# ProPrj_100MHz__2024-06-24.net
KiCad netlist of a schematic drawn in EasyEDA Pro
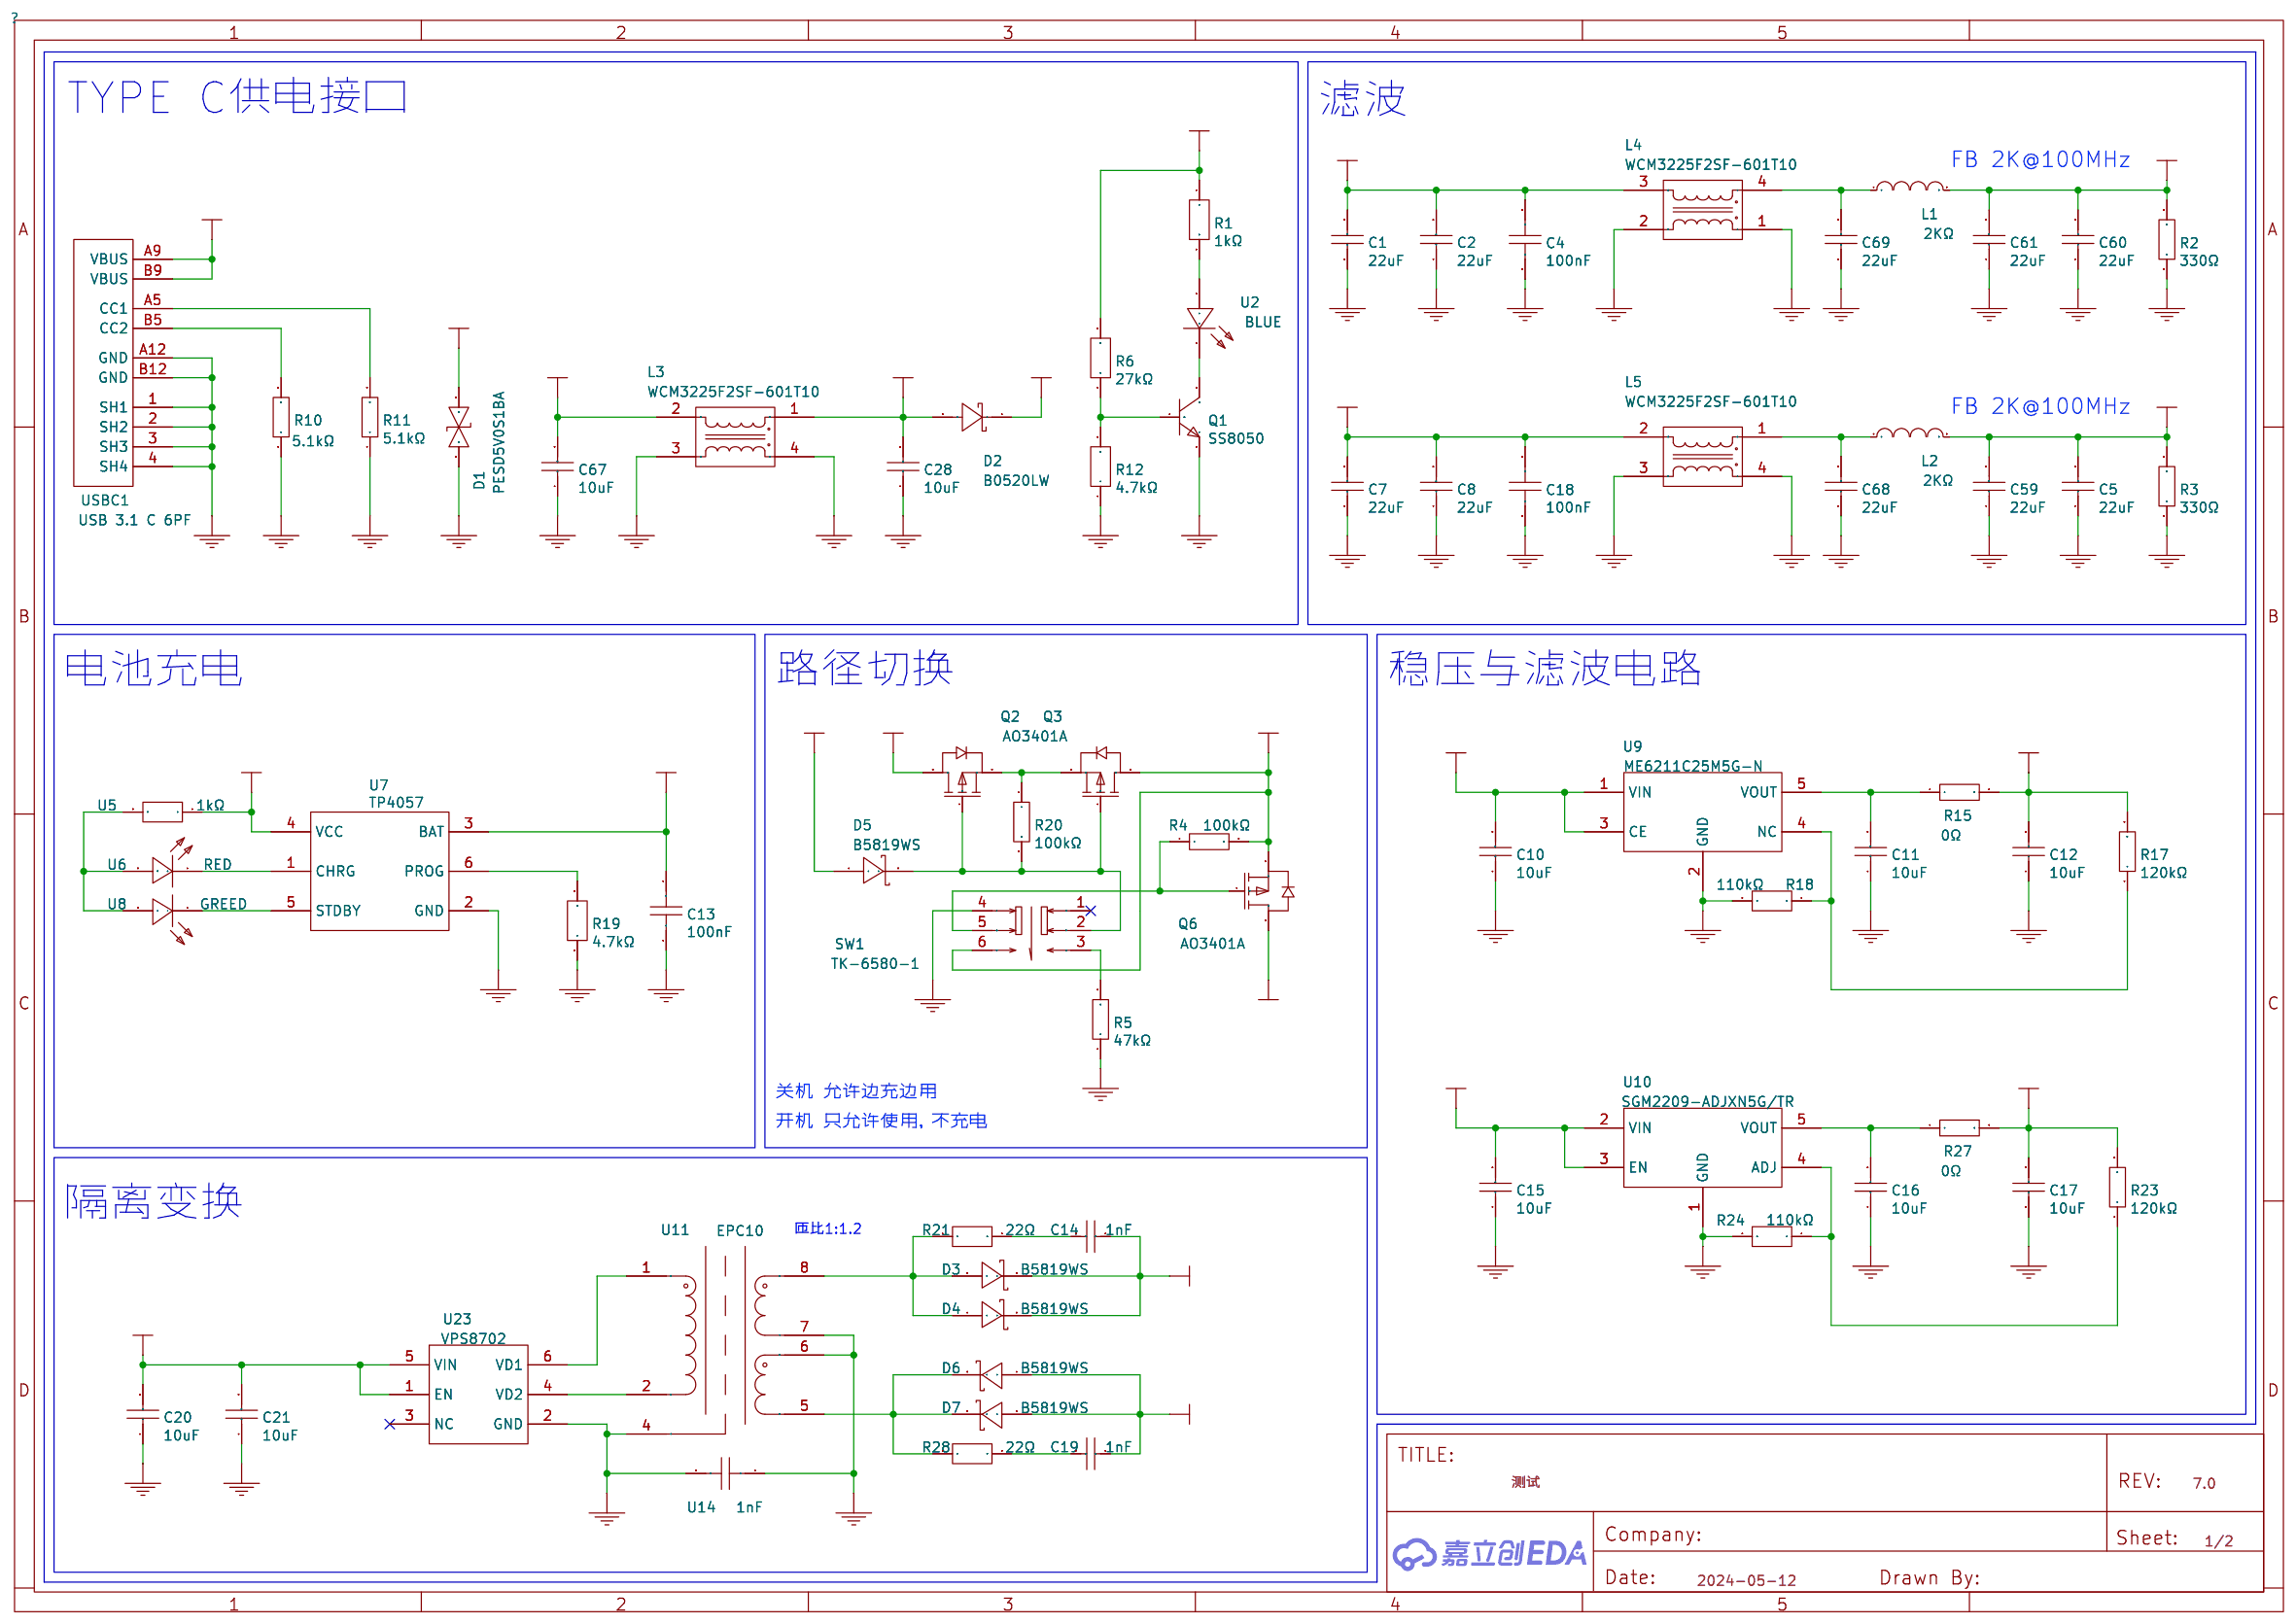
[diagram p0: 充电管理与隔离变换]
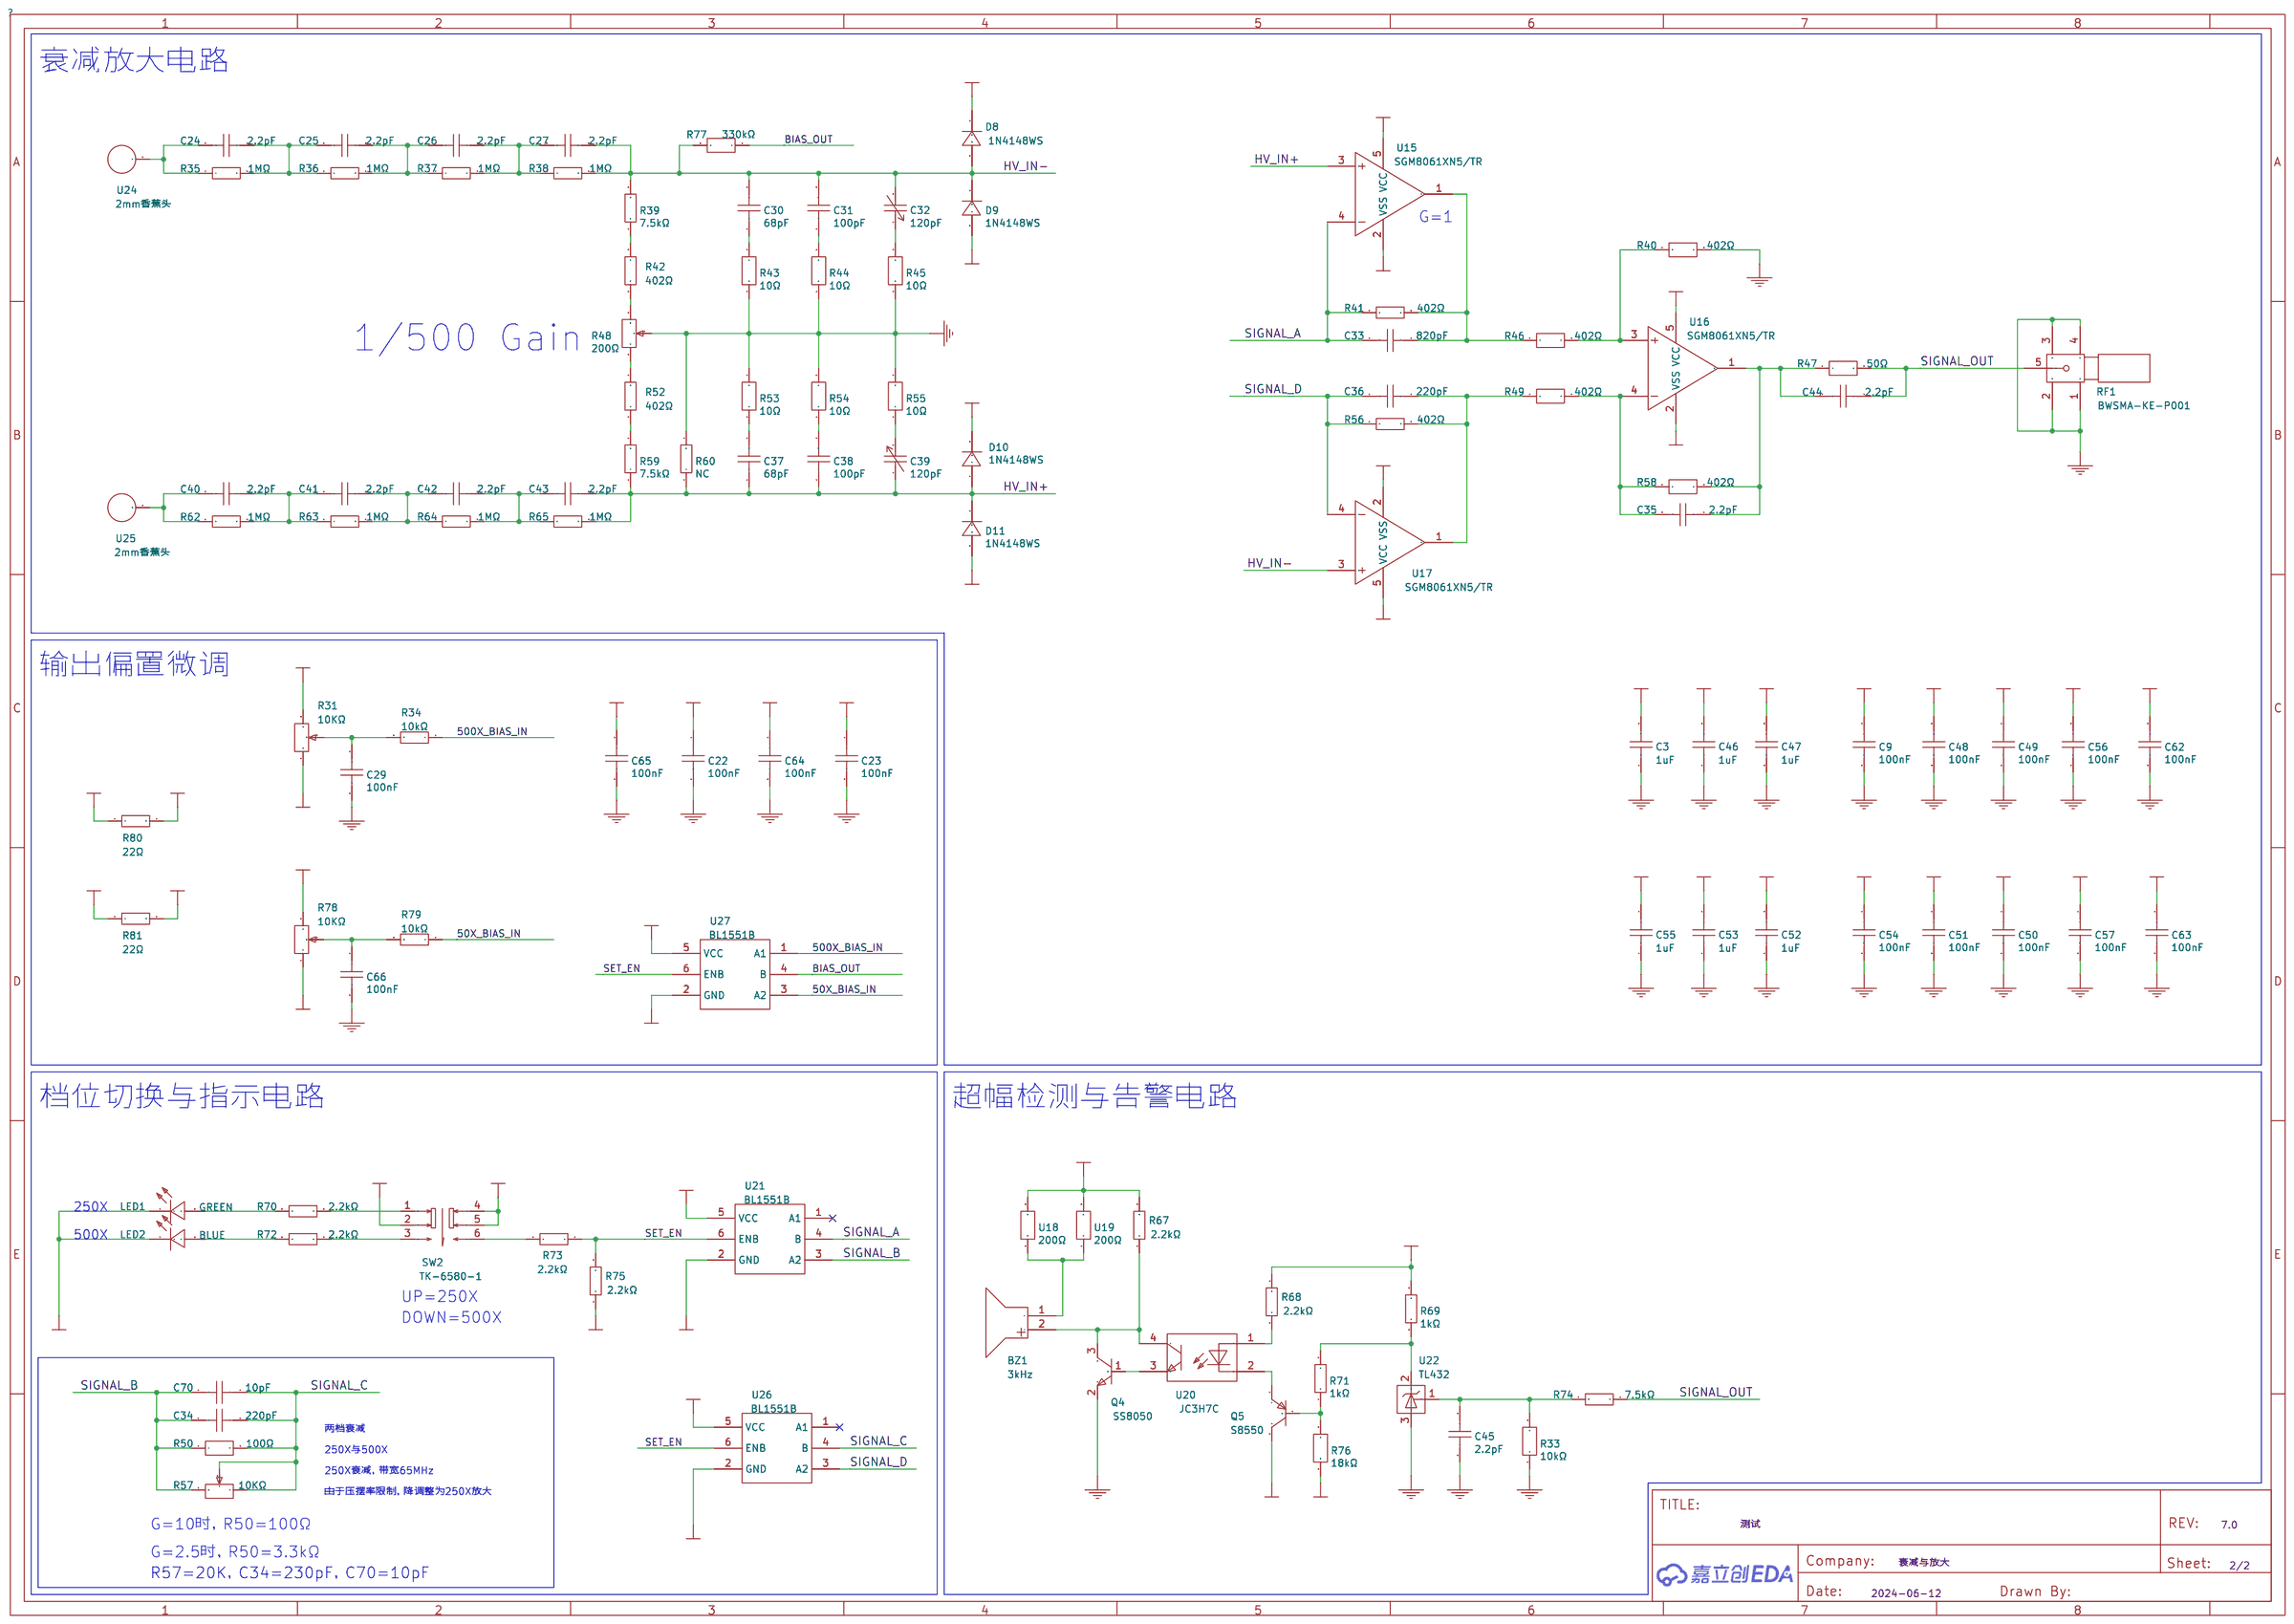
[diagram p1: 衰减与放大]

(export (version "E")
  (design (tool "Eeschema 10.0.6"))
  (components
    (comp (ref "C1")
      (value "22uF")
      (fields
        (field (name "Manufacturer Part") "CC0603MRX5R5BB226")
        (field (name "Manufacturer") "YAGEO(国巨)")
      )
      (libsource (lib "easyedapro") (part "22uF"))
    )
    (comp (ref "C2")
      (value "22uF")
      (fields
        (field (name "Manufacturer Part") "CC0603MRX5R5BB226")
        (field (name "Manufacturer") "YAGEO(国巨)")
      )
      (libsource (lib "easyedapro") (part "22uF"))
    )
    (comp (ref "C4")
      (value "100nF")
      (fields (field (name "Manufacturer Part") "0603B104K160NT") (field (name "Manufacturer") "FH(风华)"))
      (libsource (lib "easyedapro") (part "100nF"))
    )
    (comp (ref "C5")
      (value "22uF")
      (fields
        (field (name "Manufacturer Part") "CC0603MRX5R5BB226")
        (field (name "Manufacturer") "YAGEO(国巨)")
      )
      (libsource (lib "easyedapro") (part "22uF"))
    )
    (comp (ref "C7")
      (value "22uF")
      (fields
        (field (name "Manufacturer Part") "CC0603MRX5R5BB226")
        (field (name "Manufacturer") "YAGEO(国巨)")
      )
      (libsource (lib "easyedapro") (part "22uF"))
    )
    (comp (ref "C8")
      (value "22uF")
      (fields
        (field (name "Manufacturer Part") "CC0603MRX5R5BB226")
        (field (name "Manufacturer") "YAGEO(国巨)")
      )
      (libsource (lib "easyedapro") (part "22uF"))
    )
    (comp (ref "C10")
      (value "10uF")
      (fields
        (field (name "Manufacturer Part") "CC0603MRX5R5BB106")
        (field (name "Manufacturer") "YAGEO(国巨)")
      )
      (libsource (lib "easyedapro") (part "10uF"))
    )
    (comp (ref "C11")
      (value "10uF")
      (fields
        (field (name "Manufacturer Part") "CC0603MRX5R5BB106")
        (field (name "Manufacturer") "YAGEO(国巨)")
      )
      (libsource (lib "easyedapro") (part "10uF"))
    )
    (comp (ref "C12")
      (value "10uF")
      (fields
        (field (name "Manufacturer Part") "CC0603MRX5R5BB106")
        (field (name "Manufacturer") "YAGEO(国巨)")
      )
      (libsource (lib "easyedapro") (part "10uF"))
    )
    (comp (ref "C13")
      (value "100nF")
      (fields (field (name "Manufacturer Part") "0603B104K160NT") (field (name "Manufacturer") "FH(风华)"))
      (libsource (lib "easyedapro") (part "100nF"))
    )
    (comp (ref "C14")
      (value "1nF")
      (fields (field (name "Manufacturer Part") "0603CG102F500NT") (field (name "Manufacturer") "FH(风华)"))
      (libsource (lib "easyedapro") (part "1nF"))
    )
    (comp (ref "C15")
      (value "10uF")
      (fields
        (field (name "Manufacturer Part") "CC0603MRX5R5BB106")
        (field (name "Manufacturer") "YAGEO(国巨)")
      )
      (libsource (lib "easyedapro") (part "10uF"))
    )
    (comp (ref "C16")
      (value "10uF")
      (fields
        (field (name "Manufacturer Part") "CC0603MRX5R5BB106")
        (field (name "Manufacturer") "YAGEO(国巨)")
      )
      (libsource (lib "easyedapro") (part "10uF"))
    )
    (comp (ref "C17")
      (value "10uF")
      (fields
        (field (name "Manufacturer Part") "CC0603MRX5R5BB106")
        (field (name "Manufacturer") "YAGEO(国巨)")
      )
      (libsource (lib "easyedapro") (part "10uF"))
    )
    (comp (ref "C18")
      (value "100nF")
      (fields (field (name "Manufacturer Part") "0603B104K160NT") (field (name "Manufacturer") "FH(风华)"))
      (libsource (lib "easyedapro") (part "100nF"))
    )
    (comp (ref "C19")
      (value "1nF")
      (fields (field (name "Manufacturer Part") "0603CG102F500NT") (field (name "Manufacturer") "FH(风华)"))
      (libsource (lib "easyedapro") (part "1nF"))
    )
    (comp (ref "C20")
      (value "10uF")
      (fields
        (field (name "Manufacturer Part") "CC0603MRX5R5BB106")
        (field (name "Manufacturer") "YAGEO(国巨)")
      )
      (libsource (lib "easyedapro") (part "10uF"))
    )
    (comp (ref "C21")
      (value "10uF")
      (fields
        (field (name "Manufacturer Part") "CC0603MRX5R5BB106")
        (field (name "Manufacturer") "YAGEO(国巨)")
      )
      (libsource (lib "easyedapro") (part "10uF"))
    )
    (comp (ref "C28")
      (value "10uF")
      (fields
        (field (name "Manufacturer Part") "CC0603MRX5R5BB106")
        (field (name "Manufacturer") "YAGEO(国巨)")
      )
      (libsource (lib "easyedapro") (part "10uF"))
    )
    (comp (ref "C59")
      (value "22uF")
      (fields
        (field (name "Manufacturer Part") "CC0603MRX5R5BB226")
        (field (name "Manufacturer") "YAGEO(国巨)")
      )
      (libsource (lib "easyedapro") (part "22uF"))
    )
    (comp (ref "C60")
      (value "22uF")
      (fields
        (field (name "Manufacturer Part") "CC0603MRX5R5BB226")
        (field (name "Manufacturer") "YAGEO(国巨)")
      )
      (libsource (lib "easyedapro") (part "22uF"))
    )
    (comp (ref "C61")
      (value "22uF")
      (fields
        (field (name "Manufacturer Part") "CC0603MRX5R5BB226")
        (field (name "Manufacturer") "YAGEO(国巨)")
      )
      (libsource (lib "easyedapro") (part "22uF"))
    )
    (comp (ref "C67")
      (value "10uF")
      (fields
        (field (name "Manufacturer Part") "CC0603MRX5R5BB106")
        (field (name "Manufacturer") "YAGEO(国巨)")
      )
      (libsource (lib "easyedapro") (part "10uF"))
    )
    (comp (ref "C68")
      (value "22uF")
      (fields
        (field (name "Manufacturer Part") "CC0603MRX5R5BB226")
        (field (name "Manufacturer") "YAGEO(国巨)")
      )
      (libsource (lib "easyedapro") (part "22uF"))
    )
    (comp (ref "C69")
      (value "22uF")
      (fields
        (field (name "Manufacturer Part") "CC0603MRX5R5BB226")
        (field (name "Manufacturer") "YAGEO(国巨)")
      )
      (libsource (lib "easyedapro") (part "22uF"))
    )
    (comp (ref "D1")
      (value "PESD5V0S1BA")
      (fields (field (name "Manufacturer") "TECH PUBLIC(台舟)"))
      (libsource (lib "easyedapro") (part "PESD5V0S1BA"))
    )
    (comp (ref "D2")
      (value "B0520LW")
      (fields (field (name "Manufacturer") "CJ(江苏长电/长晶)"))
      (libsource (lib "easyedapro") (part "B0520LW"))
    )
    (comp (ref "D3")
      (value "B5819WS")
      (fields (field (name "Manufacturer") "CJ(江苏长电/长晶)"))
      (libsource (lib "easyedapro") (part "B5819WS"))
    )
    (comp (ref "D4")
      (value "B5819WS")
      (fields (field (name "Manufacturer") "CJ(江苏长电/长晶)"))
      (libsource (lib "easyedapro") (part "B5819WS"))
    )
    (comp (ref "D5")
      (value "B5819WS")
      (fields (field (name "Manufacturer") "CJ(江苏长电/长晶)"))
      (libsource (lib "easyedapro") (part "B5819WS"))
    )
    (comp (ref "D6")
      (value "B5819WS")
      (fields (field (name "Manufacturer") "CJ(江苏长电/长晶)"))
      (libsource (lib "easyedapro") (part "B5819WS"))
    )
    (comp (ref "D7")
      (value "B5819WS")
      (fields (field (name "Manufacturer") "CJ(江苏长电/长晶)"))
      (libsource (lib "easyedapro") (part "B5819WS"))
    )
    (comp (ref "L1")
      (value "2KΩ")
      (fields (field (name "Manufacturer Part") "GZ1608D202TF") (field (name "Manufacturer") "Sunlord(顺络)"))
      (libsource (lib "easyedapro") (part "2KΩ"))
    )
    (comp (ref "L2")
      (value "2KΩ")
      (fields (field (name "Manufacturer Part") "GZ1608D202TF") (field (name "Manufacturer") "Sunlord(顺络)"))
      (libsource (lib "easyedapro") (part "2KΩ"))
    )
    (comp (ref "L3")
      (value "WCM3225F2SF-601T10")
      (footprint "easyedapro:FILTER-SMD_4P-L3.2-W2.5-TL-1")
      (description "线路数:2;阻抗 @ 频率:600Ω@100MHz;直流电阻(DCR):200mΩ;")
      (fields (field (name "Manufacturer") "TAI-TECH(台庆)"))
      (libsource (lib "easyedapro") (part "WCM3225F2SF-601T10"))
    )
    (comp (ref "L4")
      (value "WCM3225F2SF-601T10")
      (footprint "easyedapro:FILTER-SMD_4P-L3.2-W2.5-TL-1")
      (description "线路数:2;阻抗 @ 频率:600Ω@100MHz;直流电阻(DCR):200mΩ;")
      (fields (field (name "Manufacturer") "TAI-TECH(台庆)"))
      (libsource (lib "easyedapro") (part "WCM3225F2SF-601T10"))
    )
    (comp (ref "L5")
      (value "WCM3225F2SF-601T10")
      (footprint "easyedapro:FILTER-SMD_4P-L3.2-W2.5-TL-1")
      (description "线路数:2;阻抗 @ 频率:600Ω@100MHz;直流电阻(DCR):200mΩ;")
      (fields (field (name "Manufacturer") "TAI-TECH(台庆)"))
      (libsource (lib "easyedapro") (part "WCM3225F2SF-601T10"))
    )
    (comp (ref "Q1")
      (value "SS8050")
      (fields (field (name "Manufacturer Part") "SS8050-G") (field (name "Manufacturer") "CJ(江苏长电/长晶)"))
      (libsource (lib "easyedapro") (part "SS8050"))
    )
    (comp (ref "Q2")
      (value "AO3401A")
      (fields (field (name "Manufacturer") "UMW(友台半导体)"))
      (libsource (lib "") (part "AO3401A_2"))
    )
    (comp (ref "Q3")
      (value "AO3401A")
      (fields (field (name "Manufacturer") "UMW(友台半导体)"))
      (libsource (lib "easyedapro") (part "AO3401A"))
    )
    (comp (ref "Q6")
      (value "AO3401A")
      (fields (field (name "Manufacturer") "UMW(友台半导体)"))
      (libsource (lib "") (part "AO3401A_1"))
    )
    (comp (ref "R1")
      (value "1kΩ")
      (fields (field (name "Manufacturer Part") "RT0603BRB071KL") (field (name "Manufacturer") "YAGEO(国巨)"))
      (libsource (lib "easyedapro") (part "1kΩ"))
    )
    (comp (ref "R2")
      (value "330Ω")
      (fields (field (name "Manufacturer Part") "AF0603FR-07330RL") (field (name "Manufacturer") "YAGEO(国巨)"))
      (libsource (lib "easyedapro") (part "330Ω"))
    )
    (comp (ref "R3")
      (value "330Ω")
      (fields (field (name "Manufacturer Part") "AF0603FR-07330RL") (field (name "Manufacturer") "YAGEO(国巨)"))
      (libsource (lib "easyedapro") (part "330Ω"))
    )
    (comp (ref "R4")
      (value "100kΩ")
      (fields (field (name "Manufacturer Part") "AF0603JR-07100KL") (field (name "Manufacturer") "YAGEO(国巨)"))
      (libsource (lib "easyedapro") (part "100kΩ"))
    )
    (comp (ref "R5")
      (value "47kΩ")
      (fields (field (name "Manufacturer Part") "AF0603JR-07100KL") (field (name "Manufacturer") "YAGEO(国巨)"))
      (libsource (lib "easyedapro") (part "47kΩ"))
    )
    (comp (ref "R6")
      (value "27kΩ")
      (fields (field (name "Manufacturer Part") "AC0603DR-0727KL") (field (name "Manufacturer") "YAGEO(国巨)"))
      (libsource (lib "easyedapro") (part "27kΩ"))
    )
    (comp (ref "R10")
      (value "5.1kΩ")
      (fields
        (field (name "Manufacturer Part") "0603WAF5101T5E")
        (field (name "Manufacturer") "UNI-ROYAL(厚声)")
      )
      (libsource (lib "easyedapro") (part "5.1kΩ"))
    )
    (comp (ref "R11")
      (value "5.1kΩ")
      (fields
        (field (name "Manufacturer Part") "0603WAF5101T5E")
        (field (name "Manufacturer") "UNI-ROYAL(厚声)")
      )
      (libsource (lib "easyedapro") (part "5.1kΩ"))
    )
    (comp (ref "R12")
      (value "4.7kΩ")
      (fields (field (name "Manufacturer Part") "RT0603CRE074K7L") (field (name "Manufacturer") "YAGEO(国巨)"))
      (libsource (lib "easyedapro") (part "4.7kΩ"))
    )
    (comp (ref "R15")
      (value "0Ω")
      (fields (field (name "Manufacturer Part") "RC0603FR-070RL") (field (name "Manufacturer") "YAGEO(国巨)"))
      (libsource (lib "easyedapro") (part "0Ω"))
    )
    (comp (ref "R17")
      (value "120kΩ")
      (fields
        (field (name "Manufacturer Part") "AC0603FR-07120KL")
        (field (name "Manufacturer") "UNI-ROYAL(厚声)")
      )
      (libsource (lib "easyedapro") (part "120kΩ"))
    )
    (comp (ref "R18")
      (value "110kΩ")
      (fields
        (field (name "Manufacturer Part") "0603WAD1103T5E")
        (field (name "Manufacturer") "UNI-ROYAL(厚声)")
      )
      (libsource (lib "easyedapro") (part "110kΩ"))
    )
    (comp (ref "R19")
      (value "4.7kΩ")
      (fields (field (name "Manufacturer Part") "RT0603CRE074K7L") (field (name "Manufacturer") "YAGEO(国巨)"))
      (libsource (lib "easyedapro") (part "4.7kΩ"))
    )
    (comp (ref "R20")
      (value "100kΩ")
      (fields (field (name "Manufacturer Part") "AF0603JR-07100KL") (field (name "Manufacturer") "YAGEO(国巨)"))
      (libsource (lib "easyedapro") (part "100kΩ"))
    )
    (comp (ref "R21")
      (value "22Ω")
      (fields (field (name "Manufacturer Part") "AC0603DR-0722RL") (field (name "Manufacturer") "YAGEO(国巨)"))
      (libsource (lib "easyedapro") (part "22Ω"))
    )
    (comp (ref "R23")
      (value "120kΩ")
      (fields
        (field (name "Manufacturer Part") "AC0603FR-07120KL")
        (field (name "Manufacturer") "UNI-ROYAL(厚声)")
      )
      (libsource (lib "easyedapro") (part "120kΩ"))
    )
    (comp (ref "R24")
      (value "110kΩ")
      (fields
        (field (name "Manufacturer Part") "0603WAD1103T5E")
        (field (name "Manufacturer") "UNI-ROYAL(厚声)")
      )
      (libsource (lib "easyedapro") (part "110kΩ"))
    )
    (comp (ref "R27")
      (value "0Ω")
      (fields (field (name "Manufacturer Part") "RC0603FR-070RL") (field (name "Manufacturer") "YAGEO(国巨)"))
      (libsource (lib "easyedapro") (part "0Ω"))
    )
    (comp (ref "R28")
      (value "22Ω")
      (fields (field (name "Manufacturer Part") "AC0603DR-0722RL") (field (name "Manufacturer") "YAGEO(国巨)"))
      (libsource (lib "easyedapro") (part "22Ω"))
    )
    (comp (ref "SW1")
      (value "TK-6580-1")
      (fields (field (name "Manufacturer") "Yuandi(元迪)"))
      (libsource (lib "easyedapro") (part "TK-6580-1"))
    )
    (comp (ref "U2")
      (value "BLUE")
      (fields (field (name "Manufacturer Part") "BLUEled-0603"))
      (libsource (lib "easyedapro") (part "BLUE"))
    )
    (comp (ref "U5")
      (value "1kΩ")
      (fields (field (name "Manufacturer Part") "RT0603BRB071KL") (field (name "Manufacturer") "YAGEO(国巨)"))
      (libsource (lib "easyedapro") (part "1kΩ"))
    )
    (comp (ref "U6")
      (value "RED")
      (fields (field (name "Manufacturer Part") "RED-LED_0603"))
      (libsource (lib "easyedapro") (part "RED"))
    )
    (comp (ref "U7")
      (value "TP4057")
      (fields
        (field (name "Manufacturer Part") "TP4057-42-SOT26-R")
        (field (name "Manufacturer") "TOPPOWER(南京拓微)")
      )
      (libsource (lib "easyedapro") (part "TP4057"))
    )
    (comp (ref "U8")
      (value "GREED")
      (fields (field (name "Manufacturer Part") "NCD0603O3") (field (name "Manufacturer") "国星光电"))
      (libsource (lib "easyedapro") (part "GREED"))
    )
    (comp (ref "U9")
      (value "ME6211C25M5G-N")
      (fields (field (name "Manufacturer") "MICRONE(南京微盟)"))
      (libsource (lib "easyedapro") (part "ME6211C25M5G-N"))
    )
    (comp (ref "U10") (value "SGM2209-ADJXN5G/TR") (libsource (lib "easyedapro") (part "SGM2209-ADJXN5G/TR")))
    (comp (ref "U11") (value "EPC10") (libsource (lib "easyedapro") (part "EPC10")))
    (comp (ref "U14")
      (value "1nF")
      (fields
        (field (name "Manufacturer Part") "SCC1808X102K502T")
        (field (name "Manufacturer") "IHHEC(禾伸堂)")
      )
      (libsource (lib "") (part "1nF_1"))
    )
    (comp (ref "U23")
      (value "VPS8702")
      (fields (field (name "Manufacturer") "VPSC(源特科技)"))
      (libsource (lib "easyedapro") (part "VPS8702"))
    )
    (comp (ref "USBC1")
      (value "USB 3.1 C 6PF")
      (fields (field (name "Manufacturer Part") "918-418K2023S40005") (field (name "Manufacturer") "精拓金"))
      (libsource (lib "easyedapro") (part "USB 3.1 C 6PF"))
    )
    (comp (ref "BZ1")
      (value "3kHz")
      (fields (field (name "Manufacturer Part") "HNB09A03") (field (name "Manufacturer") "华能"))
      (libsource (lib "easyedapro") (part "3kHz"))
    )
    (comp (ref "C3")
      (value "1uF")
      (fields
        (field (name "Manufacturer Part") "AC0603KRX7R6BB105")
        (field (name "Manufacturer") "YAGEO(国巨)")
      )
      (libsource (lib "easyedapro") (part "1uF"))
    )
    (comp (ref "C9")
      (value "100nF")
      (fields (field (name "Manufacturer Part") "0603B104K160NT") (field (name "Manufacturer") "FH(风华)"))
      (libsource (lib "easyedapro") (part "100nF"))
    )
    (comp (ref "C22")
      (value "100nF")
      (fields (field (name "Manufacturer Part") "0603B104K160NT") (field (name "Manufacturer") "FH(风华)"))
      (libsource (lib "easyedapro") (part "100nF"))
    )
    (comp (ref "C23")
      (value "100nF")
      (fields (field (name "Manufacturer Part") "0603B104K160NT") (field (name "Manufacturer") "FH(风华)"))
      (libsource (lib "easyedapro") (part "100nF"))
    )
    (comp (ref "C24")
      (value "2.2pF")
      (fields (field (name "Manufacturer Part") "1206N2R2C102CT") (field (name "Manufacturer") "Walsin(华新科)"))
      (libsource (lib "easyedapro") (part "2.2pF"))
    )
    (comp (ref "C25")
      (value "2.2pF")
      (fields (field (name "Manufacturer Part") "1206N2R2C102CT") (field (name "Manufacturer") "Walsin(华新科)"))
      (libsource (lib "easyedapro") (part "2.2pF"))
    )
    (comp (ref "C26")
      (value "2.2pF")
      (fields (field (name "Manufacturer Part") "1206N2R2C102CT") (field (name "Manufacturer") "Walsin(华新科)"))
      (libsource (lib "easyedapro") (part "2.2pF"))
    )
    (comp (ref "C27")
      (value "2.2pF")
      (fields (field (name "Manufacturer Part") "1206N2R2C102CT") (field (name "Manufacturer") "Walsin(华新科)"))
      (libsource (lib "easyedapro") (part "2.2pF"))
    )
    (comp (ref "C29")
      (value "100nF")
      (fields (field (name "Manufacturer Part") "0603B104K160NT") (field (name "Manufacturer") "FH(风华)"))
      (libsource (lib "easyedapro") (part "100nF"))
    )
    (comp (ref "C30")
      (value "68pF")
      (fields
        (field (name "Manufacturer Part") "CC0603GRNPO9BN680")
        (field (name "Manufacturer") "YAGEO(国巨)")
      )
      (libsource (lib "easyedapro") (part "68pF"))
    )
    (comp (ref "C31")
      (value "100pF")
      (fields
        (field (name "Manufacturer Part") "AC0603JRNPO9BN101")
        (field (name "Manufacturer") "YAGEO(国巨)")
      )
      (libsource (lib "easyedapro") (part "100pF"))
    )
    (comp (ref "C32") (value "120pF") (libsource (lib "easyedapro") (part "120pF")))
    (comp (ref "C33")
      (value "820pF")
      (fields
        (field (name "Manufacturer Part") "CC0603FRNPO0BN220")
        (field (name "Manufacturer") "YAGEO(国巨)")
      )
      (libsource (lib "easyedapro") (part "22pF"))
    )
    (comp (ref "C34")
      (value "220pF")
      (fields
        (field (name "Manufacturer Part") "CC0402JRNPO9BN221")
        (field (name "Manufacturer") "YAGEO(国巨)")
      )
      (libsource (lib "easyedapro") (part "22pF"))
    )
    (comp (ref "C35")
      (value "2.2pF")
      (fields
        (field (name "Manufacturer Part") "CC0603GRNPO0BN100")
        (field (name "Manufacturer") "YAGEO(国巨)")
      )
      (libsource (lib "") (part "10pF_2"))
    )
    (comp (ref "C36")
      (value "220pF")
      (fields
        (field (name "Manufacturer Part") "CC0603FRNPO0BN220")
        (field (name "Manufacturer") "YAGEO(国巨)")
      )
      (libsource (lib "easyedapro") (part "22pF"))
    )
    (comp (ref "C37")
      (value "68pF")
      (fields
        (field (name "Manufacturer Part") "CC0603GRNPO9BN680")
        (field (name "Manufacturer") "YAGEO(国巨)")
      )
      (libsource (lib "easyedapro") (part "68pF"))
    )
    (comp (ref "C38")
      (value "100pF")
      (fields
        (field (name "Manufacturer Part") "AC0603JRNPO9BN101")
        (field (name "Manufacturer") "YAGEO(国巨)")
      )
      (libsource (lib "easyedapro") (part "100pF"))
    )
    (comp (ref "C39") (value "120pF") (libsource (lib "easyedapro") (part "120pF")))
    (comp (ref "C40")
      (value "2.2pF")
      (fields (field (name "Manufacturer Part") "1206N2R2C102CT") (field (name "Manufacturer") "Walsin(华新科)"))
      (libsource (lib "easyedapro") (part "2.2pF"))
    )
    (comp (ref "C41")
      (value "2.2pF")
      (fields (field (name "Manufacturer Part") "1206N2R2C102CT") (field (name "Manufacturer") "Walsin(华新科)"))
      (libsource (lib "easyedapro") (part "2.2pF"))
    )
    (comp (ref "C42")
      (value "2.2pF")
      (fields (field (name "Manufacturer Part") "1206N2R2C102CT") (field (name "Manufacturer") "Walsin(华新科)"))
      (libsource (lib "easyedapro") (part "2.2pF"))
    )
    (comp (ref "C43")
      (value "2.2pF")
      (fields (field (name "Manufacturer Part") "1206N2R2C102CT") (field (name "Manufacturer") "Walsin(华新科)"))
      (libsource (lib "easyedapro") (part "2.2pF"))
    )
    (comp (ref "C44")
      (value "2.2pF")
      (fields
        (field (name "Manufacturer Part") "CC0603GRNPO0BN100")
        (field (name "Manufacturer") "YAGEO(国巨)")
        (field (name "Tolerance") "±2%")
      )
      (libsource (lib "easyedapro") (part "10pF"))
    )
    (comp (ref "C45")
      (value "2.2pF")
      (fields
        (field (name "Manufacturer Part") "CC0603KRNPO9BN100")
        (field (name "Manufacturer") "YAGEO(国巨)")
      )
      (libsource (lib "") (part "10pF_1"))
    )
    (comp (ref "C46")
      (value "1uF")
      (fields
        (field (name "Manufacturer Part") "AC0603KRX7R6BB105")
        (field (name "Manufacturer") "YAGEO(国巨)")
      )
      (libsource (lib "easyedapro") (part "1uF"))
    )
    (comp (ref "C47")
      (value "1uF")
      (fields
        (field (name "Manufacturer Part") "AC0603KRX7R6BB105")
        (field (name "Manufacturer") "YAGEO(国巨)")
      )
      (libsource (lib "easyedapro") (part "1uF"))
    )
    (comp (ref "C48")
      (value "100nF")
      (fields (field (name "Manufacturer Part") "0603B104K160NT") (field (name "Manufacturer") "FH(风华)"))
      (libsource (lib "easyedapro") (part "100nF"))
    )
    (comp (ref "C49")
      (value "100nF")
      (fields (field (name "Manufacturer Part") "0603B104K160NT") (field (name "Manufacturer") "FH(风华)"))
      (libsource (lib "easyedapro") (part "100nF"))
    )
    (comp (ref "C50")
      (value "100nF")
      (fields (field (name "Manufacturer Part") "0603B104K160NT") (field (name "Manufacturer") "FH(风华)"))
      (libsource (lib "easyedapro") (part "100nF"))
    )
    (comp (ref "C51")
      (value "100nF")
      (fields (field (name "Manufacturer Part") "0603B104K160NT") (field (name "Manufacturer") "FH(风华)"))
      (libsource (lib "easyedapro") (part "100nF"))
    )
    (comp (ref "C52")
      (value "1uF")
      (fields
        (field (name "Manufacturer Part") "AC0603KRX7R6BB105")
        (field (name "Manufacturer") "YAGEO(国巨)")
      )
      (libsource (lib "easyedapro") (part "1uF"))
    )
    (comp (ref "C53")
      (value "1uF")
      (fields
        (field (name "Manufacturer Part") "AC0603KRX7R6BB105")
        (field (name "Manufacturer") "YAGEO(国巨)")
      )
      (libsource (lib "easyedapro") (part "1uF"))
    )
    (comp (ref "C54")
      (value "100nF")
      (fields (field (name "Manufacturer Part") "0603B104K160NT") (field (name "Manufacturer") "FH(风华)"))
      (libsource (lib "easyedapro") (part "100nF"))
    )
    (comp (ref "C55")
      (value "1uF")
      (fields
        (field (name "Manufacturer Part") "AC0603KRX7R6BB105")
        (field (name "Manufacturer") "YAGEO(国巨)")
      )
      (libsource (lib "easyedapro") (part "1uF"))
    )
    (comp (ref "C56")
      (value "100nF")
      (fields (field (name "Manufacturer Part") "0603B104K160NT") (field (name "Manufacturer") "FH(风华)"))
      (libsource (lib "easyedapro") (part "100nF"))
    )
    (comp (ref "C57")
      (value "100nF")
      (fields (field (name "Manufacturer Part") "0603B104K160NT") (field (name "Manufacturer") "FH(风华)"))
      (libsource (lib "easyedapro") (part "100nF"))
    )
    (comp (ref "C62")
      (value "100nF")
      (fields (field (name "Manufacturer Part") "0603B104K160NT") (field (name "Manufacturer") "FH(风华)"))
      (libsource (lib "easyedapro") (part "100nF"))
    )
    (comp (ref "C63")
      (value "100nF")
      (fields (field (name "Manufacturer Part") "0603B104K160NT") (field (name "Manufacturer") "FH(风华)"))
      (libsource (lib "easyedapro") (part "100nF"))
    )
    (comp (ref "C64")
      (value "100nF")
      (fields (field (name "Manufacturer Part") "0603B104K160NT") (field (name "Manufacturer") "FH(风华)"))
      (libsource (lib "easyedapro") (part "100nF"))
    )
    (comp (ref "C65")
      (value "100nF")
      (fields (field (name "Manufacturer Part") "0603B104K160NT") (field (name "Manufacturer") "FH(风华)"))
      (libsource (lib "easyedapro") (part "100nF"))
    )
    (comp (ref "C66")
      (value "100nF")
      (fields (field (name "Manufacturer Part") "0603B104K160NT") (field (name "Manufacturer") "FH(风华)"))
      (libsource (lib "easyedapro") (part "100nF"))
    )
    (comp (ref "C70")
      (value "10pF")
      (fields
        (field (name "Manufacturer Part") "CC0402JRNPO9BN100")
        (field (name "Manufacturer") "YAGEO(国巨)")
      )
      (libsource (lib "easyedapro") (part "22pF"))
    )
    (comp (ref "D8")
      (value "1N4148WS")
      (fields (field (name "Manufacturer") "Slkor(萨科微)"))
      (libsource (lib "easyedapro") (part "1N4148WS"))
    )
    (comp (ref "D9")
      (value "1N4148WS")
      (fields (field (name "Manufacturer") "Slkor(萨科微)"))
      (libsource (lib "easyedapro") (part "1N4148WS"))
    )
    (comp (ref "D10")
      (value "1N4148WS")
      (fields (field (name "Manufacturer") "Slkor(萨科微)"))
      (libsource (lib "easyedapro") (part "1N4148WS"))
    )
    (comp (ref "D11")
      (value "1N4148WS")
      (fields (field (name "Manufacturer") "Slkor(萨科微)"))
      (libsource (lib "easyedapro") (part "1N4148WS"))
    )
    (comp (ref "LED1")
      (value "GREEN")
      (fields (field (name "Manufacturer Part") "BLUEled-0603"))
      (libsource (lib "easyedapro") (part "BLUE"))
    )
    (comp (ref "LED2")
      (value "BLUE")
      (fields (field (name "Manufacturer Part") "BLUEled-0603"))
      (libsource (lib "easyedapro") (part "BLUE"))
    )
    (comp (ref "Q4")
      (value "SS8050")
      (fields (field (name "Manufacturer") "YONGYUTAI(永裕泰)"))
      (libsource (lib "easyedapro") (part "S8050"))
    )
    (comp (ref "Q5")
      (value "S8550")
      (fields (field (name "Manufacturer Part") "AD-SS8550") (field (name "Manufacturer") "CJ(江苏长电/长晶)"))
      (libsource (lib "easyedapro") (part "S8550"))
    )
    (comp (ref "R31") (value "10KΩ") (libsource (lib "easyedapro") (part "1KΩ")))
    (comp (ref "R33")
      (value "10kΩ")
      (fields (field (name "Manufacturer Part") "AC0603FR-0710KL") (field (name "Manufacturer") "YAGEO(国巨)"))
      (libsource (lib "easyedapro") (part "10kΩ"))
    )
    (comp (ref "R34")
      (value "10kΩ")
      (fields (field (name "Manufacturer Part") "AC0603FR-07330KL") (field (name "Manufacturer") "YAGEO(国巨)"))
      (libsource (lib "easyedapro") (part "330KΩ"))
    )
    (comp (ref "R35")
      (value "1MΩ")
      (fields (field (name "Manufacturer Part") "RC1206JR-071ML") (field (name "Manufacturer") "YAGEO(国巨)"))
      (libsource (lib "easyedapro") (part "1MΩ"))
    )
    (comp (ref "R36")
      (value "1MΩ")
      (fields (field (name "Manufacturer Part") "RC1206JR-071ML") (field (name "Manufacturer") "YAGEO(国巨)"))
      (libsource (lib "easyedapro") (part "1MΩ"))
    )
    (comp (ref "R37")
      (value "1MΩ")
      (fields (field (name "Manufacturer Part") "RC1206JR-071ML") (field (name "Manufacturer") "YAGEO(国巨)"))
      (libsource (lib "easyedapro") (part "1MΩ"))
    )
    (comp (ref "R38")
      (value "1MΩ")
      (fields (field (name "Manufacturer Part") "RC1206JR-071ML") (field (name "Manufacturer") "YAGEO(国巨)"))
      (libsource (lib "easyedapro") (part "1MΩ"))
    )
    (comp (ref "R39")
      (value "7.5kΩ")
      (fields (field (name "Manufacturer Part") "RC0603JR-077K5L") (field (name "Manufacturer") "YAGEO(国巨)"))
      (libsource (lib "easyedapro") (part "7.5kΩ"))
    )
    (comp (ref "R40")
      (value "402Ω")
      (fields
        (field (name "Manufacturer Part") "0603WAF4020T5E")
        (field (name "Manufacturer") "UNI-ROYAL(厚声)")
      )
      (libsource (lib "easyedapro") (part "402Ω"))
    )
    (comp (ref "R41")
      (value "402Ω")
      (fields
        (field (name "Manufacturer Part") "0603WAF4020T5E")
        (field (name "Manufacturer") "UNI-ROYAL(厚声)")
      )
      (libsource (lib "") (part "402Ω_1"))
    )
    (comp (ref "R42")
      (value "402Ω")
      (fields
        (field (name "Manufacturer Part") "0603WAF4020T5E")
        (field (name "Manufacturer") "UNI-ROYAL(厚声)")
      )
      (libsource (lib "") (part "402Ω_1"))
    )
    (comp (ref "R43")
      (value "10Ω")
      (fields (field (name "Manufacturer Part") "AC0603DR-0710RL") (field (name "Manufacturer") "YAGEO(国巨)"))
      (libsource (lib "easyedapro") (part "10Ω"))
    )
    (comp (ref "R44")
      (value "10Ω")
      (fields (field (name "Manufacturer Part") "AC0603DR-0710RL") (field (name "Manufacturer") "YAGEO(国巨)"))
      (libsource (lib "easyedapro") (part "10Ω"))
    )
    (comp (ref "R45")
      (value "10Ω")
      (fields (field (name "Manufacturer Part") "AC0603DR-0710RL") (field (name "Manufacturer") "YAGEO(国巨)"))
      (libsource (lib "easyedapro") (part "10Ω"))
    )
    (comp (ref "R46")
      (value "402Ω")
      (fields
        (field (name "Manufacturer Part") "0603WAF4020T5E")
        (field (name "Manufacturer") "UNI-ROYAL(厚声)")
      )
      (libsource (lib "easyedapro") (part "402Ω"))
    )
    (comp (ref "R47")
      (value "50Ω")
      (fields (field (name "Manufacturer Part") "RC0603JR-07150RL") (field (name "Manufacturer") "YAGEO(国巨)"))
      (libsource (lib "easyedapro") (part "150Ω"))
    )
    (comp (ref "R48") (value "200Ω") (libsource (lib "easyedapro") (part "500Ω")))
    (comp (ref "R49")
      (value "402Ω")
      (fields
        (field (name "Manufacturer Part") "0603WAF4020T5E")
        (field (name "Manufacturer") "UNI-ROYAL(厚声)")
      )
      (libsource (lib "easyedapro") (part "402Ω"))
    )
    (comp (ref "R50")
      (value "100Ω")
      (fields (field (name "Manufacturer Part") "RT0603CRD07100RL") (field (name "Manufacturer") "YAGEO(国巨)"))
      (libsource (lib "easyedapro") (part "100Ω"))
    )
    (comp (ref "R52")
      (value "402Ω")
      (fields
        (field (name "Manufacturer Part") "0603WAF4020T5E")
        (field (name "Manufacturer") "UNI-ROYAL(厚声)")
      )
      (libsource (lib "") (part "402Ω_1"))
    )
    (comp (ref "R53")
      (value "10Ω")
      (fields (field (name "Manufacturer Part") "AC0603DR-0710RL") (field (name "Manufacturer") "YAGEO(国巨)"))
      (libsource (lib "easyedapro") (part "10Ω"))
    )
    (comp (ref "R54")
      (value "10Ω")
      (fields (field (name "Manufacturer Part") "AC0603DR-0710RL") (field (name "Manufacturer") "YAGEO(国巨)"))
      (libsource (lib "easyedapro") (part "10Ω"))
    )
    (comp (ref "R55")
      (value "10Ω")
      (fields (field (name "Manufacturer Part") "AC0603DR-0710RL") (field (name "Manufacturer") "YAGEO(国巨)"))
      (libsource (lib "easyedapro") (part "10Ω"))
    )
    (comp (ref "R56")
      (value "402Ω")
      (fields
        (field (name "Manufacturer Part") "0603WAF4020T5E")
        (field (name "Manufacturer") "UNI-ROYAL(厚声)")
      )
      (libsource (lib "") (part "402Ω_1"))
    )
    (comp (ref "R57") (value "10KΩ") (libsource (lib "easyedapro") (part "10KΩ")))
    (comp (ref "R58")
      (value "402Ω")
      (fields
        (field (name "Manufacturer Part") "0603WAF4020T5E")
        (field (name "Manufacturer") "UNI-ROYAL(厚声)")
      )
      (libsource (lib "easyedapro") (part "402Ω"))
    )
    (comp (ref "R59")
      (value "7.5kΩ")
      (fields (field (name "Manufacturer Part") "RC0603JR-077K5L") (field (name "Manufacturer") "YAGEO(国巨)"))
      (libsource (lib "easyedapro") (part "7.5kΩ"))
    )
    (comp (ref "R60") (value "NC") (libsource (lib "easyedapro") (part "NC")))
    (comp (ref "R62")
      (value "1MΩ")
      (fields (field (name "Manufacturer Part") "RC1206JR-071ML") (field (name "Manufacturer") "YAGEO(国巨)"))
      (libsource (lib "easyedapro") (part "1MΩ"))
    )
    (comp (ref "R63")
      (value "1MΩ")
      (fields (field (name "Manufacturer Part") "RC1206JR-071ML") (field (name "Manufacturer") "YAGEO(国巨)"))
      (libsource (lib "easyedapro") (part "1MΩ"))
    )
    (comp (ref "R64")
      (value "1MΩ")
      (fields (field (name "Manufacturer Part") "RC1206JR-071ML") (field (name "Manufacturer") "YAGEO(国巨)"))
      (libsource (lib "easyedapro") (part "1MΩ"))
    )
    (comp (ref "R65")
      (value "1MΩ")
      (fields (field (name "Manufacturer Part") "RC1206JR-071ML") (field (name "Manufacturer") "YAGEO(国巨)"))
      (libsource (lib "easyedapro") (part "1MΩ"))
    )
    (comp (ref "R67")
      (value "2.2kΩ")
      (fields
        (field (name "Manufacturer Part") "0603WAF2201T5E")
        (field (name "Manufacturer") "UNI-ROYAL(厚声)")
      )
      (libsource (lib "easyedapro") (part "2.2kΩ"))
    )
    (comp (ref "R68")
      (value "2.2kΩ")
      (fields
        (field (name "Manufacturer Part") "0603WAF2201T5E")
        (field (name "Manufacturer") "UNI-ROYAL(厚声)")
      )
      (libsource (lib "easyedapro") (part "2.2kΩ"))
    )
    (comp (ref "R69")
      (value "1kΩ")
      (fields (field (name "Manufacturer Part") "RC0603FR-071KL") (field (name "Manufacturer") "YAGEO(国巨)"))
      (libsource (lib "easyedapro") (part "1kΩ"))
    )
    (comp (ref "R70")
      (value "2.2kΩ")
      (fields
        (field (name "Manufacturer Part") "0603WAF2201T5E")
        (field (name "Manufacturer") "UNI-ROYAL(厚声)")
      )
      (libsource (lib "easyedapro") (part "2.2kΩ"))
    )
    (comp (ref "R71")
      (value "1kΩ")
      (fields (field (name "Manufacturer Part") "RC0603FR-071KL") (field (name "Manufacturer") "YAGEO(国巨)"))
      (libsource (lib "easyedapro") (part "1kΩ"))
    )
    (comp (ref "R72")
      (value "2.2kΩ")
      (fields
        (field (name "Manufacturer Part") "0603WAF2201T5E")
        (field (name "Manufacturer") "UNI-ROYAL(厚声)")
      )
      (libsource (lib "easyedapro") (part "2.2kΩ"))
    )
    (comp (ref "R73")
      (value "2.2kΩ")
      (fields
        (field (name "Manufacturer Part") "0603WAF2201T5E")
        (field (name "Manufacturer") "UNI-ROYAL(厚声)")
      )
      (libsource (lib "easyedapro") (part "2.2kΩ"))
    )
    (comp (ref "R74")
      (value "7.5kΩ")
      (fields (field (name "Manufacturer Part") "RC0603JR-077K5L") (field (name "Manufacturer") "YAGEO(国巨)"))
      (libsource (lib "easyedapro") (part "7.5kΩ"))
    )
    (comp (ref "R75")
      (value "2.2kΩ")
      (fields
        (field (name "Manufacturer Part") "0603WAF2201T5E")
        (field (name "Manufacturer") "UNI-ROYAL(厚声)")
      )
      (libsource (lib "easyedapro") (part "2.2kΩ"))
    )
    (comp (ref "R76")
      (value "18kΩ")
      (fields (field (name "Manufacturer Part") "RT0603BRE0718KL") (field (name "Manufacturer") "YAGEO(国巨)"))
      (libsource (lib "easyedapro") (part "18kΩ"))
    )
    (comp (ref "R77")
      (value "330kΩ")
      (fields
        (field (name "Manufacturer Part") "0603WAD1103T5E")
        (field (name "Manufacturer") "UNI-ROYAL(厚声)")
      )
      (libsource (lib "easyedapro") (part "110kΩ"))
    )
    (comp (ref "R78") (value "10KΩ") (libsource (lib "easyedapro") (part "1KΩ")))
    (comp (ref "R79")
      (value "10kΩ")
      (fields (field (name "Manufacturer Part") "AC0603FR-07330KL") (field (name "Manufacturer") "YAGEO(国巨)"))
      (libsource (lib "easyedapro") (part "330KΩ"))
    )
    (comp (ref "R80")
      (value "22Ω")
      (footprint "easyedapro:R0603")
      (description "电阻类型:厚膜电阻;阻值:22Ω;精度:±1%;功率:100mW;最大工作电压:75V;温度系数:±100ppm/°C;")
      (fields
        (field (name "Manufacturer Part") "0603WAF220JT5E")
        (field (name "Manufacturer") "UNI-ROYAL(厚声)")
      )
      (libsource (lib "easyedapro") (part "0603WAF220JT5E"))
    )
    (comp (ref "R81")
      (value "22Ω")
      (footprint "easyedapro:R0603")
      (description "电阻类型:厚膜电阻;阻值:22Ω;精度:±1%;功率:100mW;最大工作电压:75V;温度系数:±100ppm/°C;")
      (fields
        (field (name "Manufacturer Part") "0603WAF220JT5E")
        (field (name "Manufacturer") "UNI-ROYAL(厚声)")
      )
      (libsource (lib "easyedapro") (part "0603WAF220JT5E"))
    )
    (comp (ref "RF1")
      (value "BWSMA-KE-P001")
      (fields (field (name "Manufacturer") "BAT WIRELESS(蝙蝠无线)"))
      (libsource (lib "easyedapro") (part "BWSMA-KE-P001"))
    )
    (comp (ref "SW2")
      (value "TK-6580-1")
      (fields (field (name "Manufacturer") "Yuandi(元迪)"))
      (libsource (lib "easyedapro") (part "TK-6580-1"))
    )
    (comp (ref "U15")
      (value "SGM8061XN5/TR")
      (fields (field (name "Manufacturer") "SGMICRO(圣邦微)"))
      (libsource (lib "easyedapro") (part "SGM8061XN5/TR"))
    )
    (comp (ref "U16")
      (value "SGM8061XN5/TR")
      (fields (field (name "Manufacturer") "SGMICRO(圣邦微)"))
      (libsource (lib "easyedapro") (part "SGM8061XN5/TR"))
    )
    (comp (ref "U17")
      (value "SGM8061XN5/TR")
      (fields (field (name "Manufacturer") "SGMICRO(圣邦微)"))
      (libsource (lib "easyedapro") (part "SGM8061XN5/TR"))
    )
    (comp (ref "U18")
      (value "200Ω")
      (fields (field (name "Manufacturer Part") "RT0603BRD07200RL") (field (name "Manufacturer") "YAGEO(国巨)"))
      (libsource (lib "easyedapro") (part "200Ω"))
    )
    (comp (ref "U19")
      (value "200Ω")
      (fields (field (name "Manufacturer Part") "RT0603BRD07200RL") (field (name "Manufacturer") "YAGEO(国巨)"))
      (libsource (lib "easyedapro") (part "200Ω"))
    )
    (comp (ref "U20")
      (value "JC3H7C")
      (fields (field (name "Manufacturer Part") "JC3H7"))
      (libsource (lib "easyedapro") (part "JC3H7C"))
    )
    (comp (ref "U21")
      (value "BL1551B")
      (fields (field (name "Manufacturer") "BL(上海贝岭)"))
      (libsource (lib "easyedapro") (part "BL1551B"))
    )
    (comp (ref "U22")
      (value "TL432")
      (fields (field (name "Manufacturer") "GOODWORK(固得沃克)"))
      (libsource (lib "easyedapro") (part "TL432"))
    )
    (comp (ref "U24") (value "2mm香蕉头") (libsource (lib "easyedapro") (part "2mm香蕉头")))
    (comp (ref "U25") (value "2mm香蕉头") (libsource (lib "easyedapro") (part "2mm香蕉头")))
    (comp (ref "U26")
      (value "BL1551B")
      (fields (field (name "Manufacturer") "BL(上海贝岭)"))
      (libsource (lib "easyedapro") (part "BL1551B"))
    )
    (comp (ref "U27")
      (value "BL1551B")
      (fields (field (name "Manufacturer") "BL(上海贝岭)"))
      (libsource (lib "easyedapro") (part "BL1551B"))
    )
  )
  (nets
    (net (code "1") (name "+2.5V") (class "Default")
      (node (ref "C12") (pin "2") (pinfunction "2_2") (pintype "input"))
      (node (ref "C3") (pin "2") (pinfunction "2_2") (pintype "unspecified"))
      (node (ref "C46") (pin "2") (pinfunction "2_2") (pintype "unspecified"))
      (node (ref "C47") (pin "2") (pinfunction "2_2") (pintype "unspecified"))
      (node (ref "C48") (pin "1") (pinfunction "1_1") (pintype "unspecified"))
      (node (ref "C49") (pin "1") (pinfunction "1_1") (pintype "unspecified"))
      (node (ref "C56") (pin "1") (pinfunction "1_1") (pintype "unspecified"))
      (node (ref "C62") (pin "1") (pinfunction "1_1") (pintype "unspecified"))
      (node (ref "C64") (pin "1") (pinfunction "1_1") (pintype "unspecified"))
      (node (ref "C9") (pin "1") (pinfunction "1_1") (pintype "unspecified"))
      (node (ref "D10") (pin "2") (pinfunction "2_2") (pintype "unspecified"))
      (node (ref "D8") (pin "2") (pinfunction "2_2") (pintype "unspecified"))
      (node (ref "R15") (pin "2") (pinfunction "2_2") (pintype "input"))
      (node (ref "R17") (pin "2") (pinfunction "2_2") (pintype "input"))
      (node (ref "R80") (pin "1") (pinfunction "1_1") (pintype "input"))
      (node (ref "SW2") (pin "4") (pinfunction "4_4") (pintype "unspecified"))
      (node (ref "SW2") (pin "5") (pinfunction "5_5") (pintype "unspecified"))
      (node (ref "U15") (pin "5") (pinfunction "VCC_5") (pintype "unspecified"))
      (node (ref "U16") (pin "5") (pinfunction "VCC_5") (pintype "unspecified"))
      (node (ref "U17") (pin "5") (pinfunction "VCC_5") (pintype "unspecified"))
      (node (ref "U21") (pin "5") (pinfunction "VCC_5") (pintype "unspecified"))
      (node (ref "U26") (pin "5") (pinfunction "VCC_5") (pintype "unspecified"))
      (node (ref "U27") (pin "5") (pinfunction "VCC_5") (pintype "unspecified"))
    )
    (net (code "2") (name "+4.5V") (class "Default")
      (node (ref "C10") (pin "2") (pinfunction "2_2") (pintype "input"))
      (node (ref "C60") (pin "2") (pinfunction "2_2") (pintype "input"))
      (node (ref "C61") (pin "2") (pinfunction "2_2") (pintype "input"))
      (node (ref "L1") (pin "2") (pinfunction "2_2") (pintype "unspecified"))
      (node (ref "R2") (pin "2") (pinfunction "2_2") (pintype "input"))
      (node (ref "R68") (pin "2") (pinfunction "2_2") (pintype "input"))
      (node (ref "R69") (pin "2") (pinfunction "2_2") (pintype "input"))
      (node (ref "SW2") (pin "2") (pinfunction "2_2") (pintype "unspecified"))
      (node (ref "U9") (pin "1") (pinfunction "VIN_1") (pintype "unspecified"))
      (node (ref "U9") (pin "3") (pinfunction "CE_3") (pintype "unspecified"))
    )
    (net (code "3") (name "+5V") (class "Default")
      (node (ref "C20") (pin "2") (pinfunction "2_2") (pintype "input"))
      (node (ref "C21") (pin "2") (pinfunction "2_2") (pintype "input"))
      (node (ref "D2") (pin "1") (pinfunction "K_1") (pintype "unspecified"))
      (node (ref "Q3") (pin "3") (pinfunction "D_3") (pintype "unspecified"))
      (node (ref "Q6") (pin "2") (pinfunction "S_2") (pintype "unspecified"))
      (node (ref "R1") (pin "1") (pinfunction "1_1") (pintype "unspecified"))
      (node (ref "R4") (pin "2") (pinfunction "2_2") (pintype "unspecified"))
      (node (ref "R6") (pin "2") (pinfunction "2_2") (pintype "unspecified"))
      (node (ref "R67") (pin "2") (pinfunction "2_2") (pintype "input"))
      (node (ref "SW1") (pin "6") (pinfunction "6_6") (pintype "unspecified"))
      (node (ref "U18") (pin "2") (pinfunction "2_2") (pintype "unspecified"))
      (node (ref "U19") (pin "2") (pinfunction "2_2") (pintype "unspecified"))
      (node (ref "U23") (pin "1") (pinfunction "EN_1") (pintype "unspecified"))
      (node (ref "U23") (pin "5") (pinfunction "VIN_5") (pintype "unspecified"))
    )
    (net (code "4") (name "+VCC") (class "Default")
      (node (ref "C1") (pin "2") (pinfunction "2_2") (pintype "input"))
      (node (ref "C14") (pin "2") (pinfunction "2_2") (pintype "input"))
      (node (ref "C2") (pin "2") (pinfunction "2_2") (pintype "input"))
      (node (ref "C4") (pin "1") (pinfunction "1_1") (pintype "unspecified"))
      (node (ref "D3") (pin "2") (pinfunction "K_2") (pintype "unspecified"))
      (node (ref "D4") (pin "2") (pinfunction "K_2") (pintype "unspecified"))
      (node (ref "L4") (pin "3") (pinfunction "3_3") (pintype "unspecified"))
    )
    (net (code "5") (name "-2.5V") (class "Default")
      (node (ref "C17") (pin "2") (pinfunction "2_2") (pintype "input"))
      (node (ref "C50") (pin "1") (pinfunction "1_1") (pintype "unspecified"))
      (node (ref "C51") (pin "1") (pinfunction "1_1") (pintype "unspecified"))
      (node (ref "C52") (pin "2") (pinfunction "2_2") (pintype "unspecified"))
      (node (ref "C53") (pin "2") (pinfunction "2_2") (pintype "unspecified"))
      (node (ref "C54") (pin "1") (pinfunction "1_1") (pintype "unspecified"))
      (node (ref "C55") (pin "2") (pinfunction "2_2") (pintype "unspecified"))
      (node (ref "C57") (pin "1") (pinfunction "1_1") (pintype "unspecified"))
      (node (ref "C63") (pin "1") (pinfunction "1_1") (pintype "unspecified"))
      (node (ref "C65") (pin "1") (pinfunction "1_1") (pintype "unspecified"))
      (node (ref "D11") (pin "1") (pinfunction "1_1") (pintype "unspecified"))
      (node (ref "D9") (pin "1") (pinfunction "1_1") (pintype "unspecified"))
      (node (ref "R23") (pin "2") (pinfunction "2_2") (pintype "input"))
      (node (ref "R27") (pin "2") (pinfunction "2_2") (pintype "input"))
      (node (ref "R75") (pin "1") (pinfunction "1_1") (pintype "input"))
      (node (ref "R81") (pin "1") (pinfunction "1_1") (pintype "input"))
      (node (ref "U15") (pin "2") (pinfunction "VSS_2") (pintype "unspecified"))
      (node (ref "U16") (pin "2") (pinfunction "VSS_2") (pintype "unspecified"))
      (node (ref "U17") (pin "2") (pinfunction "VSS_2") (pintype "unspecified"))
      (node (ref "U21") (pin "2") (pinfunction "GND_2") (pintype "unspecified"))
      (node (ref "U26") (pin "2") (pinfunction "GND_2") (pintype "unspecified"))
      (node (ref "U27") (pin "2") (pinfunction "GND_2") (pintype "unspecified"))
    )
    (net (code "6") (name "-4.5V") (class "Default")
      (node (ref "C15") (pin "2") (pinfunction "2_2") (pintype "input"))
      (node (ref "C5") (pin "2") (pinfunction "2_2") (pintype "input"))
      (node (ref "C59") (pin "2") (pinfunction "2_2") (pintype "input"))
      (node (ref "L2") (pin "2") (pinfunction "2_2") (pintype "unspecified"))
      (node (ref "LED1") (pin "1") (pinfunction "K_1") (pintype "unspecified"))
      (node (ref "LED2") (pin "1") (pinfunction "K_1") (pintype "unspecified"))
      (node (ref "Q5") (pin "3") (pinfunction "C_3") (pintype "unspecified"))
      (node (ref "R3") (pin "2") (pinfunction "2_2") (pintype "input"))
      (node (ref "R76") (pin "1") (pinfunction "1_1") (pintype "unspecified"))
      (node (ref "U10") (pin "2") (pinfunction "VIN_2") (pintype "unspecified"))
      (node (ref "U10") (pin "3") (pinfunction "EN_3") (pintype "unspecified"))
    )
    (net (code "7") (name "-VCC") (class "Default")
      (node (ref "C18") (pin "1") (pinfunction "1_1") (pintype "unspecified"))
      (node (ref "C19") (pin "2") (pinfunction "2_2") (pintype "input"))
      (node (ref "C7") (pin "2") (pinfunction "2_2") (pintype "input"))
      (node (ref "C8") (pin "2") (pinfunction "2_2") (pintype "input"))
      (node (ref "D6") (pin "1") (pinfunction "A_1") (pintype "unspecified"))
      (node (ref "D7") (pin "1") (pinfunction "A_1") (pintype "unspecified"))
      (node (ref "L5") (pin "2") (pinfunction "2_2") (pintype "unspecified"))
    )
    (net (code "8") (name "50X_BIAS_IN") (class "Default")
      (node (ref "R79") (pin "1") (pinfunction "1_1") (pintype "unspecified"))
      (node (ref "U27") (pin "3") (pinfunction "A2_3") (pintype "unspecified"))
    )
    (net (code "9") (name "500X_BIAS_IN") (class "Default")
      (node (ref "R34") (pin "1") (pinfunction "1_1") (pintype "unspecified"))
      (node (ref "U27") (pin "1") (pinfunction "A1_1") (pintype "unspecified"))
    )
    (net (code "10") (name "BAT+") (class "Default")
      (node (ref "C13") (pin "1") (pinfunction "1_1") (pintype "unspecified"))
      (node (ref "Q2") (pin "3") (pinfunction "D_3") (pintype "unspecified"))
      (node (ref "U7") (pin "3") (pinfunction "BAT_3") (pintype "unspecified"))
    )
    (net (code "11") (name "BAT_CHRG") (class "Default")
      (node (ref "Q6") (pin "3") (pinfunction "D_3") (pintype "unspecified"))
      (node (ref "U5") (pin "1") (pinfunction "1_1") (pintype "unspecified"))
      (node (ref "U7") (pin "4") (pinfunction "VCC_4") (pintype "unspecified"))
    )
    (net (code "12") (name "BIAS_OUT") (class "Default")
      (node (ref "R77") (pin "1") (pinfunction "1_1") (pintype "unspecified"))
      (node (ref "U27") (pin "4") (pinfunction "B_4") (pintype "unspecified"))
    )
    (net (code "13") (name "EGND") (class "Default")
      (node (ref "C67") (pin "1") (pinfunction "1_1") (pintype "input"))
      (node (ref "D1") (pin "1") (pinfunction "1_1") (pintype "unspecified"))
      (node (ref "L3") (pin "3") (pinfunction "3_3") (pintype "unspecified"))
      (node (ref "R10") (pin "1") (pinfunction "1_1") (pintype "input"))
      (node (ref "R11") (pin "1") (pinfunction "1_1") (pintype "input"))
      (node (ref "USBC1") (pin "1") (pinfunction "SH1_1") (pintype "unspecified"))
      (node (ref "USBC1") (pin "2") (pinfunction "SH2_2") (pintype "unspecified"))
      (node (ref "USBC1") (pin "3") (pinfunction "SH3_3") (pintype "unspecified"))
      (node (ref "USBC1") (pin "4") (pinfunction "SH4_4") (pintype "unspecified"))
      (node (ref "USBC1") (pin "A12") (pinfunction "GND_A12") (pintype "unspecified"))
      (node (ref "USBC1") (pin "B12") (pinfunction "GND_B12") (pintype "unspecified"))
    )
    (net (code "14") (name "GND") (class "Default")
      (node (ref "C10") (pin "1") (pinfunction "1_1") (pintype "input"))
      (node (ref "C11") (pin "1") (pinfunction "1_1") (pintype "input"))
      (node (ref "C12") (pin "1") (pinfunction "1_1") (pintype "input"))
      (node (ref "C15") (pin "1") (pinfunction "1_1") (pintype "input"))
      (node (ref "C16") (pin "1") (pinfunction "1_1") (pintype "input"))
      (node (ref "C17") (pin "1") (pinfunction "1_1") (pintype "input"))
      (node (ref "C22") (pin "2") (pinfunction "2_2") (pintype "unspecified"))
      (node (ref "C23") (pin "2") (pinfunction "2_2") (pintype "unspecified"))
      (node (ref "C29") (pin "2") (pinfunction "2_2") (pintype "unspecified"))
      (node (ref "C3") (pin "1") (pinfunction "1_1") (pintype "unspecified"))
      (node (ref "C45") (pin "2") (pinfunction "2_2") (pintype "unspecified"))
      (node (ref "C46") (pin "1") (pinfunction "1_1") (pintype "unspecified"))
      (node (ref "C47") (pin "1") (pinfunction "1_1") (pintype "unspecified"))
      (node (ref "C48") (pin "2") (pinfunction "2_2") (pintype "unspecified"))
      (node (ref "C49") (pin "2") (pinfunction "2_2") (pintype "unspecified"))
      (node (ref "C5") (pin "1") (pinfunction "1_1") (pintype "input"))
      (node (ref "C50") (pin "2") (pinfunction "2_2") (pintype "unspecified"))
      (node (ref "C51") (pin "2") (pinfunction "2_2") (pintype "unspecified"))
      (node (ref "C52") (pin "1") (pinfunction "1_1") (pintype "unspecified"))
      (node (ref "C53") (pin "1") (pinfunction "1_1") (pintype "unspecified"))
      (node (ref "C54") (pin "2") (pinfunction "2_2") (pintype "unspecified"))
      (node (ref "C55") (pin "1") (pinfunction "1_1") (pintype "unspecified"))
      (node (ref "C56") (pin "2") (pinfunction "2_2") (pintype "unspecified"))
      (node (ref "C57") (pin "2") (pinfunction "2_2") (pintype "unspecified"))
      (node (ref "C59") (pin "1") (pinfunction "1_1") (pintype "input"))
      (node (ref "C60") (pin "1") (pinfunction "1_1") (pintype "input"))
      (node (ref "C61") (pin "1") (pinfunction "1_1") (pintype "input"))
      (node (ref "C62") (pin "2") (pinfunction "2_2") (pintype "unspecified"))
      (node (ref "C63") (pin "2") (pinfunction "2_2") (pintype "unspecified"))
      (node (ref "C64") (pin "2") (pinfunction "2_2") (pintype "unspecified"))
      (node (ref "C65") (pin "2") (pinfunction "2_2") (pintype "unspecified"))
      (node (ref "C66") (pin "2") (pinfunction "2_2") (pintype "unspecified"))
      (node (ref "C68") (pin "1") (pinfunction "1_1") (pintype "input"))
      (node (ref "C69") (pin "1") (pinfunction "1_1") (pintype "input"))
      (node (ref "C9") (pin "2") (pinfunction "2_2") (pintype "unspecified"))
      (node (ref "L4") (pin "1") (pinfunction "1_1") (pintype "unspecified"))
      (node (ref "L5") (pin "4") (pinfunction "4_4") (pintype "unspecified"))
      (node (ref "R18") (pin "2") (pinfunction "2_2") (pintype "unspecified"))
      (node (ref "R2") (pin "1") (pinfunction "1_1") (pintype "input"))
      (node (ref "R24") (pin "2") (pinfunction "2_2") (pintype "unspecified"))
      (node (ref "R3") (pin "1") (pinfunction "1_1") (pintype "input"))
      (node (ref "R33") (pin "1") (pinfunction "1_1") (pintype "unspecified"))
      (node (ref "R40") (pin "2") (pinfunction "2_2") (pintype "unspecified"))
      (node (ref "R43") (pin "1") (pinfunction "1_1") (pintype "unspecified"))
      (node (ref "R44") (pin "1") (pinfunction "1_1") (pintype "unspecified"))
      (node (ref "R45") (pin "1") (pinfunction "1_1") (pintype "unspecified"))
      (node (ref "R48") (pin "2") (pinfunction "2_2") (pintype "input"))
      (node (ref "R53") (pin "2") (pinfunction "2_2") (pintype "unspecified"))
      (node (ref "R54") (pin "2") (pinfunction "2_2") (pintype "unspecified"))
      (node (ref "R55") (pin "2") (pinfunction "2_2") (pintype "unspecified"))
      (node (ref "R60") (pin "2") (pinfunction "2_2") (pintype "unspecified"))
      (node (ref "RF1") (pin "1") (pinfunction "1_1") (pintype "unspecified"))
      (node (ref "RF1") (pin "2") (pinfunction "2_2") (pintype "unspecified"))
      (node (ref "RF1") (pin "3") (pinfunction "3_3") (pintype "unspecified"))
      (node (ref "RF1") (pin "4") (pinfunction "4_4") (pintype "unspecified"))
      (node (ref "U10") (pin "1") (pinfunction "GND_1") (pintype "unspecified"))
      (node (ref "U22") (pin "3") (pinfunction "A_3") (pintype "unspecified"))
      (node (ref "U9") (pin "2") (pinfunction "GND_2") (pintype "unspecified"))
    )
    (net (code "15") (name "HV_IN+") (class "Default")
      (node (ref "C37") (pin "1") (pinfunction "1_1") (pintype "unspecified"))
      (node (ref "C38") (pin "1") (pinfunction "1_1") (pintype "unspecified"))
      (node (ref "C39") (pin "1") (pinfunction "1_1") (pintype "input"))
      (node (ref "C43") (pin "1") (pinfunction "1_1") (pintype "unspecified"))
      (node (ref "D10") (pin "1") (pinfunction "1_1") (pintype "unspecified"))
      (node (ref "D11") (pin "2") (pinfunction "2_2") (pintype "unspecified"))
      (node (ref "R59") (pin "1") (pinfunction "1_1") (pintype "input"))
      (node (ref "R60") (pin "1") (pinfunction "1_1") (pintype "unspecified"))
      (node (ref "R65") (pin "2") (pinfunction "2_2") (pintype "unspecified"))
      (node (ref "U15") (pin "3") (pinfunction "3_3") (pintype "unspecified"))
    )
    (net (code "16") (name "HV_IN-") (class "Default")
      (node (ref "C27") (pin "1") (pinfunction "1_1") (pintype "unspecified"))
      (node (ref "C30") (pin "2") (pinfunction "2_2") (pintype "unspecified"))
      (node (ref "C31") (pin "2") (pinfunction "2_2") (pintype "unspecified"))
      (node (ref "C32") (pin "1") (pinfunction "1_1") (pintype "input"))
      (node (ref "D8") (pin "1") (pinfunction "1_1") (pintype "unspecified"))
      (node (ref "D9") (pin "2") (pinfunction "2_2") (pintype "unspecified"))
      (node (ref "R38") (pin "2") (pinfunction "2_2") (pintype "unspecified"))
      (node (ref "R39") (pin "2") (pinfunction "2_2") (pintype "input"))
      (node (ref "R77") (pin "2") (pinfunction "2_2") (pintype "unspecified"))
      (node (ref "U17") (pin "3") (pinfunction "3_3") (pintype "unspecified"))
    )
    (net (code "17") (name "Net-(BZ1-+)") (class "Default")
      (node (ref "BZ1") (pin "1") (pinfunction "+_1") (pintype "unspecified"))
      (node (ref "U18") (pin "1") (pinfunction "1_1") (pintype "unspecified"))
      (node (ref "U19") (pin "1") (pinfunction "1_1") (pintype "unspecified"))
    )
    (net (code "18") (name "Net-(BZ1--)") (class "Default")
      (node (ref "BZ1") (pin "2") (pinfunction "-_2") (pintype "unspecified"))
      (node (ref "Q4") (pin "3") (pinfunction "C_3") (pintype "unspecified"))
      (node (ref "R67") (pin "1") (pinfunction "1_1") (pintype "input"))
      (node (ref "U20") (pin "4") (pinfunction "4_4") (pintype "unspecified"))
    )
    (net (code "19") (name "Net-(C14-Pad1)") (class "Default")
      (node (ref "C14") (pin "1") (pinfunction "1_1") (pintype "input"))
      (node (ref "R21") (pin "2") (pinfunction "2_2") (pintype "unspecified"))
    )
    (net (code "20") (name "Net-(C19-Pad1)") (class "Default")
      (node (ref "C19") (pin "1") (pinfunction "1_1") (pintype "input"))
      (node (ref "R28") (pin "2") (pinfunction "2_2") (pintype "unspecified"))
    )
    (net (code "21") (name "Net-(C24-Pad1)") (class "Default")
      (node (ref "C24") (pin "1") (pinfunction "1_1") (pintype "unspecified"))
      (node (ref "C25") (pin "2") (pinfunction "2_2") (pintype "unspecified"))
      (node (ref "R35") (pin "2") (pinfunction "2_2") (pintype "unspecified"))
      (node (ref "R36") (pin "1") (pinfunction "1_1") (pintype "unspecified"))
    )
    (net (code "22") (name "Net-(C24-Pad2)") (class "Default")
      (node (ref "C24") (pin "2") (pinfunction "2_2") (pintype "unspecified"))
      (node (ref "R35") (pin "1") (pinfunction "1_1") (pintype "unspecified"))
      (node (ref "U24") (pin "1") (pinfunction "1_1") (pintype "unspecified"))
    )
    (net (code "23") (name "Net-(C25-Pad1)") (class "Default")
      (node (ref "C25") (pin "1") (pinfunction "1_1") (pintype "unspecified"))
      (node (ref "C26") (pin "2") (pinfunction "2_2") (pintype "unspecified"))
      (node (ref "R36") (pin "2") (pinfunction "2_2") (pintype "unspecified"))
      (node (ref "R37") (pin "1") (pinfunction "1_1") (pintype "unspecified"))
    )
    (net (code "24") (name "Net-(C26-Pad1)") (class "Default")
      (node (ref "C26") (pin "1") (pinfunction "1_1") (pintype "unspecified"))
      (node (ref "C27") (pin "2") (pinfunction "2_2") (pintype "unspecified"))
      (node (ref "R37") (pin "2") (pinfunction "2_2") (pintype "unspecified"))
      (node (ref "R38") (pin "1") (pinfunction "1_1") (pintype "unspecified"))
    )
    (net (code "25") (name "Net-(C29-Pad1)") (class "Default")
      (node (ref "C29") (pin "1") (pinfunction "1_1") (pintype "unspecified"))
      (node (ref "R31") (pin "2") (pinfunction "2_2") (pintype "input"))
      (node (ref "R34") (pin "2") (pinfunction "2_2") (pintype "unspecified"))
    )
    (net (code "26") (name "Net-(C30-Pad1)") (class "Default")
      (node (ref "C30") (pin "1") (pinfunction "1_1") (pintype "unspecified"))
      (node (ref "R43") (pin "2") (pinfunction "2_2") (pintype "unspecified"))
    )
    (net (code "27") (name "Net-(C31-Pad1)") (class "Default")
      (node (ref "C31") (pin "1") (pinfunction "1_1") (pintype "unspecified"))
      (node (ref "R44") (pin "2") (pinfunction "2_2") (pintype "unspecified"))
    )
    (net (code "28") (name "Net-(C32-Pad2)") (class "Default")
      (node (ref "C32") (pin "2") (pinfunction "2_2") (pintype "input"))
      (node (ref "R45") (pin "2") (pinfunction "2_2") (pintype "unspecified"))
    )
    (net (code "29") (name "Net-(C33-Pad1)") (class "Default")
      (node (ref "C33") (pin "1") (pinfunction "1_1") (pintype "unspecified"))
      (node (ref "R41") (pin "2") (pinfunction "2_2") (pintype "input"))
      (node (ref "R46") (pin "1") (pinfunction "1_1") (pintype "unspecified"))
      (node (ref "U15") (pin "1") (pinfunction "1_1") (pintype "unspecified"))
    )
    (net (code "30") (name "Net-(C35-Pad1)") (class "Default")
      (node (ref "C35") (pin "1") (pinfunction "1_1") (pintype "unspecified"))
      (node (ref "C44") (pin "2") (pinfunction "2_2") (pintype "unspecified"))
      (node (ref "R47") (pin "1") (pinfunction "1_1") (pintype "unspecified"))
      (node (ref "R58") (pin "2") (pinfunction "2_2") (pintype "unspecified"))
      (node (ref "U16") (pin "1") (pinfunction "1_1") (pintype "unspecified"))
    )
    (net (code "31") (name "Net-(C35-Pad2)") (class "Default")
      (node (ref "C35") (pin "2") (pinfunction "2_2") (pintype "unspecified"))
      (node (ref "R49") (pin "2") (pinfunction "2_2") (pintype "unspecified"))
      (node (ref "R58") (pin "1") (pinfunction "1_1") (pintype "unspecified"))
      (node (ref "U16") (pin "4") (pinfunction "4_4") (pintype "unspecified"))
    )
    (net (code "32") (name "Net-(C36-Pad1)") (class "Default")
      (node (ref "C36") (pin "1") (pinfunction "1_1") (pintype "unspecified"))
      (node (ref "R49") (pin "1") (pinfunction "1_1") (pintype "unspecified"))
      (node (ref "R56") (pin "2") (pinfunction "2_2") (pintype "input"))
      (node (ref "U17") (pin "1") (pinfunction "1_1") (pintype "unspecified"))
    )
    (net (code "33") (name "Net-(C37-Pad2)") (class "Default")
      (node (ref "C37") (pin "2") (pinfunction "2_2") (pintype "unspecified"))
      (node (ref "R53") (pin "1") (pinfunction "1_1") (pintype "unspecified"))
    )
    (net (code "34") (name "Net-(C38-Pad2)") (class "Default")
      (node (ref "C38") (pin "2") (pinfunction "2_2") (pintype "unspecified"))
      (node (ref "R54") (pin "1") (pinfunction "1_1") (pintype "unspecified"))
    )
    (net (code "35") (name "Net-(C39-Pad2)") (class "Default")
      (node (ref "C39") (pin "2") (pinfunction "2_2") (pintype "input"))
      (node (ref "R55") (pin "1") (pinfunction "1_1") (pintype "unspecified"))
    )
    (net (code "36") (name "Net-(C40-Pad1)") (class "Default")
      (node (ref "C40") (pin "1") (pinfunction "1_1") (pintype "unspecified"))
      (node (ref "C41") (pin "2") (pinfunction "2_2") (pintype "unspecified"))
      (node (ref "R62") (pin "2") (pinfunction "2_2") (pintype "unspecified"))
      (node (ref "R63") (pin "1") (pinfunction "1_1") (pintype "unspecified"))
    )
    (net (code "37") (name "Net-(C40-Pad2)") (class "Default")
      (node (ref "C40") (pin "2") (pinfunction "2_2") (pintype "unspecified"))
      (node (ref "R62") (pin "1") (pinfunction "1_1") (pintype "unspecified"))
      (node (ref "U25") (pin "1") (pinfunction "1_1") (pintype "unspecified"))
    )
    (net (code "38") (name "Net-(C41-Pad1)") (class "Default")
      (node (ref "C41") (pin "1") (pinfunction "1_1") (pintype "unspecified"))
      (node (ref "C42") (pin "2") (pinfunction "2_2") (pintype "unspecified"))
      (node (ref "R63") (pin "2") (pinfunction "2_2") (pintype "unspecified"))
      (node (ref "R64") (pin "1") (pinfunction "1_1") (pintype "unspecified"))
    )
    (net (code "39") (name "Net-(C42-Pad1)") (class "Default")
      (node (ref "C42") (pin "1") (pinfunction "1_1") (pintype "unspecified"))
      (node (ref "C43") (pin "2") (pinfunction "2_2") (pintype "unspecified"))
      (node (ref "R64") (pin "2") (pinfunction "2_2") (pintype "unspecified"))
      (node (ref "R65") (pin "1") (pinfunction "1_1") (pintype "unspecified"))
    )
    (net (code "40") (name "Net-(C66-Pad1)") (class "Default")
      (node (ref "C66") (pin "1") (pinfunction "1_1") (pintype "unspecified"))
      (node (ref "R78") (pin "2") (pinfunction "2_2") (pintype "input"))
      (node (ref "R79") (pin "2") (pinfunction "2_2") (pintype "unspecified"))
    )
    (net (code "41") (name "Net-(C68-Pad2)") (class "Default")
      (node (ref "C68") (pin "2") (pinfunction "2_2") (pintype "input"))
      (node (ref "L2") (pin "1") (pinfunction "1_1") (pintype "unspecified"))
      (node (ref "L5") (pin "1") (pinfunction "1_1") (pintype "unspecified"))
    )
    (net (code "42") (name "Net-(C69-Pad2)") (class "Default")
      (node (ref "C69") (pin "2") (pinfunction "2_2") (pintype "input"))
      (node (ref "L1") (pin "1") (pinfunction "1_1") (pintype "unspecified"))
      (node (ref "L4") (pin "4") (pinfunction "4_4") (pintype "unspecified"))
    )
    (net (code "43") (name "Net-(D3-A)") (class "Default")
      (node (ref "D3") (pin "1") (pinfunction "A_1") (pintype "unspecified"))
      (node (ref "D4") (pin "1") (pinfunction "A_1") (pintype "unspecified"))
      (node (ref "R21") (pin "1") (pinfunction "1_1") (pintype "unspecified"))
      (node (ref "U11") (pin "8") (pinfunction "8_8") (pintype "unspecified"))
    )
    (net (code "44") (name "Net-(D5-K)") (class "Default")
      (node (ref "D5") (pin "2") (pinfunction "K_2") (pintype "unspecified"))
      (node (ref "Q2") (pin "1") (pinfunction "G_1") (pintype "unspecified"))
      (node (ref "Q3") (pin "1") (pinfunction "G_1") (pintype "unspecified"))
      (node (ref "R20") (pin "2") (pinfunction "2_2") (pintype "unspecified"))
      (node (ref "SW1") (pin "2") (pinfunction "2_2") (pintype "unspecified"))
    )
    (net (code "45") (name "Net-(D6-K)") (class "Default")
      (node (ref "D6") (pin "2") (pinfunction "K_2") (pintype "unspecified"))
      (node (ref "D7") (pin "2") (pinfunction "K_2") (pintype "unspecified"))
      (node (ref "R28") (pin "1") (pinfunction "1_1") (pintype "unspecified"))
      (node (ref "U11") (pin "5") (pinfunction "5_5") (pintype "unspecified"))
    )
    (net (code "46") (name "Net-(LED1-A)") (class "Default")
      (node (ref "LED1") (pin "2") (pinfunction "A_2") (pintype "unspecified"))
      (node (ref "R70") (pin "2") (pinfunction "2_2") (pintype "input"))
    )
    (net (code "47") (name "Net-(LED2-A)") (class "Default")
      (node (ref "LED2") (pin "2") (pinfunction "A_2") (pintype "unspecified"))
      (node (ref "R72") (pin "2") (pinfunction "2_2") (pintype "input"))
    )
    (net (code "48") (name "Net-(Q1-B)") (class "Default")
      (node (ref "Q1") (pin "1") (pinfunction "B_1") (pintype "input"))
      (node (ref "R12") (pin "2") (pinfunction "2_2") (pintype "unspecified"))
      (node (ref "R6") (pin "1") (pinfunction "1_1") (pintype "unspecified"))
    )
    (net (code "49") (name "Net-(Q1-C)") (class "Default")
      (node (ref "Q1") (pin "3") (pinfunction "C_3") (pintype "input"))
      (node (ref "U2") (pin "1") (pinfunction "K_1") (pintype "unspecified"))
    )
    (net (code "50") (name "Net-(Q2-S)") (class "Default")
      (node (ref "Q2") (pin "2") (pinfunction "S_2") (pintype "unspecified"))
      (node (ref "Q3") (pin "2") (pinfunction "S_2") (pintype "unspecified"))
      (node (ref "R20") (pin "1") (pinfunction "1_1") (pintype "unspecified"))
    )
    (net (code "51") (name "Net-(Q4-B)") (class "Default")
      (node (ref "Q4") (pin "1") (pinfunction "B_1") (pintype "unspecified"))
      (node (ref "U20") (pin "3") (pinfunction "3_3") (pintype "unspecified"))
    )
    (net (code "52") (name "Net-(Q5-B)") (class "Default")
      (node (ref "Q5") (pin "1") (pinfunction "B_1") (pintype "unspecified"))
      (node (ref "R71") (pin "1") (pinfunction "1_1") (pintype "input"))
      (node (ref "R76") (pin "2") (pinfunction "2_2") (pintype "unspecified"))
    )
    (net (code "53") (name "Net-(Q5-E)") (class "Default")
      (node (ref "Q5") (pin "2") (pinfunction "E_2") (pintype "unspecified"))
      (node (ref "U20") (pin "2") (pinfunction "2_2") (pintype "unspecified"))
    )
    (net (code "54") (name "Net-(Q6-G)") (class "Default")
      (node (ref "Q6") (pin "1") (pinfunction "G_1") (pintype "unspecified"))
      (node (ref "R4") (pin "1") (pinfunction "1_1") (pintype "unspecified"))
      (node (ref "SW1") (pin "5") (pinfunction "5_5") (pintype "unspecified"))
    )
    (net (code "55") (name "Net-(R5-Pad2)") (class "Default")
      (node (ref "R5") (pin "2") (pinfunction "2_2") (pintype "unspecified"))
      (node (ref "SW1") (pin "3") (pinfunction "3_3") (pintype "unspecified"))
    )
    (net (code "56") (name "Net-(R39-Pad1)") (class "Default")
      (node (ref "R39") (pin "1") (pinfunction "1_1") (pintype "input"))
      (node (ref "R42") (pin "2") (pinfunction "2_2") (pintype "input"))
    )
    (net (code "57") (name "Net-(R40-Pad1)") (class "Default")
      (node (ref "R40") (pin "1") (pinfunction "1_1") (pintype "unspecified"))
      (node (ref "R46") (pin "2") (pinfunction "2_2") (pintype "unspecified"))
      (node (ref "U16") (pin "3") (pinfunction "3_3") (pintype "unspecified"))
    )
    (net (code "58") (name "Net-(R42-Pad1)") (class "Default")
      (node (ref "R42") (pin "1") (pinfunction "1_1") (pintype "input"))
      (node (ref "R48") (pin "3") (pinfunction "3_3") (pintype "input"))
    )
    (net (code "59") (name "Net-(R48-Pad1)") (class "Default")
      (node (ref "R48") (pin "1") (pinfunction "1_1") (pintype "input"))
      (node (ref "R52") (pin "2") (pinfunction "2_2") (pintype "input"))
    )
    (net (code "60") (name "Net-(R52-Pad1)") (class "Default")
      (node (ref "R52") (pin "1") (pinfunction "1_1") (pintype "input"))
      (node (ref "R59") (pin "2") (pinfunction "2_2") (pintype "input"))
    )
    (net (code "61") (name "Net-(R68-Pad1)") (class "Default")
      (node (ref "R68") (pin "1") (pinfunction "1_1") (pintype "input"))
      (node (ref "U20") (pin "1") (pinfunction "1_1") (pintype "unspecified"))
    )
    (net (code "62") (name "Net-(R70-Pad1)") (class "Default")
      (node (ref "R70") (pin "1") (pinfunction "1_1") (pintype "input"))
      (node (ref "SW2") (pin "1") (pinfunction "1_1") (pintype "unspecified"))
    )
    (net (code "63") (name "Net-(R72-Pad1)") (class "Default")
      (node (ref "R72") (pin "1") (pinfunction "1_1") (pintype "input"))
      (node (ref "SW2") (pin "3") (pinfunction "3_3") (pintype "unspecified"))
    )
    (net (code "64") (name "Net-(R73-Pad2)") (class "Default")
      (node (ref "R73") (pin "2") (pinfunction "2_2") (pintype "input"))
      (node (ref "SW2") (pin "6") (pinfunction "6_6") (pintype "unspecified"))
    )
    (net (code "65") (name "Net-(U2-A)") (class "Default")
      (node (ref "R1") (pin "2") (pinfunction "2_2") (pintype "unspecified"))
      (node (ref "U2") (pin "2") (pinfunction "A_2") (pintype "unspecified"))
    )
    (net (code "66") (name "Net-(U7-CHRG)") (class "Default")
      (node (ref "U6") (pin "1") (pinfunction "1_1") (pintype "unspecified"))
      (node (ref "U7") (pin "1") (pinfunction "CHRG_1") (pintype "unspecified"))
    )
    (net (code "67") (name "Net-(U7-PROG)") (class "Default")
      (node (ref "R19") (pin "2") (pinfunction "2_2") (pintype "unspecified"))
      (node (ref "U7") (pin "6") (pinfunction "PROG_6") (pintype "unspecified"))
    )
    (net (code "68") (name "Net-(U7-STDBY)") (class "Default")
      (node (ref "U7") (pin "5") (pinfunction "STDBY_5") (pintype "unspecified"))
      (node (ref "U8") (pin "1") (pinfunction "-_1") (pintype "unspecified"))
    )
    (net (code "69") (name "Net-(U8-+)") (class "Default")
      (node (ref "U5") (pin "2") (pinfunction "2_2") (pintype "unspecified"))
      (node (ref "U6") (pin "2") (pinfunction "2_2") (pintype "unspecified"))
      (node (ref "U8") (pin "2") (pinfunction "+_2") (pintype "unspecified"))
    )
    (net (code "70") (name "Net-(U9-NC)") (class "Default")
      (node (ref "R17") (pin "1") (pinfunction "1_1") (pintype "input"))
      (node (ref "R18") (pin "1") (pinfunction "1_1") (pintype "unspecified"))
      (node (ref "U9") (pin "4") (pinfunction "NC_4") (pintype "unspecified"))
    )
    (net (code "71") (name "Net-(U9-VOUT)") (class "Default")
      (node (ref "C11") (pin "2") (pinfunction "2_2") (pintype "input"))
      (node (ref "R15") (pin "1") (pinfunction "1_1") (pintype "input"))
      (node (ref "U9") (pin "5") (pinfunction "VOUT_5") (pintype "unspecified"))
    )
    (net (code "72") (name "Net-(U10-ADJ)") (class "Default")
      (node (ref "R23") (pin "1") (pinfunction "1_1") (pintype "input"))
      (node (ref "R24") (pin "1") (pinfunction "1_1") (pintype "unspecified"))
      (node (ref "U10") (pin "4") (pinfunction "ADJ_4") (pintype "unspecified"))
    )
    (net (code "73") (name "Net-(U10-VOUT)") (class "Default")
      (node (ref "C16") (pin "2") (pinfunction "2_2") (pintype "input"))
      (node (ref "R27") (pin "1") (pinfunction "1_1") (pintype "input"))
      (node (ref "U10") (pin "5") (pinfunction "VOUT_5") (pintype "unspecified"))
    )
    (net (code "74") (name "Net-(U22-K)") (class "Default")
      (node (ref "R69") (pin "1") (pinfunction "1_1") (pintype "input"))
      (node (ref "R71") (pin "2") (pinfunction "2_2") (pintype "input"))
      (node (ref "U22") (pin "2") (pinfunction "K_2") (pintype "unspecified"))
    )
    (net (code "75") (name "Net-(U22-R)") (class "Default")
      (node (ref "C45") (pin "1") (pinfunction "1_1") (pintype "unspecified"))
      (node (ref "R33") (pin "2") (pinfunction "2_2") (pintype "unspecified"))
      (node (ref "R74") (pin "2") (pinfunction "2_2") (pintype "input"))
      (node (ref "U22") (pin "1") (pinfunction "R_1") (pintype "unspecified"))
    )
    (net (code "76") (name "Net-(U23-VD1)") (class "Default")
      (node (ref "U11") (pin "1") (pinfunction "1_1") (pintype "unspecified"))
      (node (ref "U23") (pin "6") (pinfunction "VD1_6") (pintype "unspecified"))
    )
    (net (code "77") (name "Net-(U23-VD2)") (class "Default")
      (node (ref "U11") (pin "2") (pinfunction "2_2") (pintype "unspecified"))
      (node (ref "U23") (pin "4") (pinfunction "VD2_4") (pintype "unspecified"))
    )
    (net (code "78") (name "Net-(USBC1-CC1)") (class "Default")
      (node (ref "R11") (pin "2") (pinfunction "2_2") (pintype "input"))
      (node (ref "USBC1") (pin "A5") (pinfunction "CC1_A5") (pintype "unspecified"))
    )
    (net (code "79") (name "Net-(USBC1-CC2)") (class "Default")
      (node (ref "R10") (pin "2") (pinfunction "2_2") (pintype "input"))
      (node (ref "USBC1") (pin "B5") (pinfunction "CC2_B5") (pintype "unspecified"))
    )
    (net (code "80") (name "PGND") (class "Default")
      (node (ref "C13") (pin "2") (pinfunction "2_2") (pintype "unspecified"))
      (node (ref "C20") (pin "1") (pinfunction "1_1") (pintype "input"))
      (node (ref "C21") (pin "1") (pinfunction "1_1") (pintype "input"))
      (node (ref "C28") (pin "1") (pinfunction "1_1") (pintype "input"))
      (node (ref "L3") (pin "4") (pinfunction "4_4") (pintype "unspecified"))
      (node (ref "Q1") (pin "2") (pinfunction "E_2") (pintype "input"))
      (node (ref "Q4") (pin "2") (pinfunction "E_2") (pintype "unspecified"))
      (node (ref "R12") (pin "1") (pinfunction "1_1") (pintype "unspecified"))
      (node (ref "R19") (pin "1") (pinfunction "1_1") (pintype "unspecified"))
      (node (ref "R5") (pin "1") (pinfunction "1_1") (pintype "unspecified"))
      (node (ref "SW1") (pin "4") (pinfunction "4_4") (pintype "unspecified"))
      (node (ref "U11") (pin "4") (pinfunction "4_4") (pintype "unspecified"))
      (node (ref "U14") (pin "2") (pinfunction "2_2") (pintype "unspecified"))
      (node (ref "U23") (pin "2") (pinfunction "GND_2") (pintype "unspecified"))
      (node (ref "U7") (pin "2") (pinfunction "GND_2") (pintype "unspecified"))
    )
    (net (code "81") (name "POWER_IN") (class "Default")
      (node (ref "C67") (pin "2") (pinfunction "2_2") (pintype "input"))
      (node (ref "D1") (pin "2") (pinfunction "2_2") (pintype "unspecified"))
      (node (ref "L3") (pin "2") (pinfunction "2_2") (pintype "unspecified"))
      (node (ref "USBC1") (pin "A9") (pinfunction "VBUS_A9") (pintype "unspecified"))
      (node (ref "USBC1") (pin "B9") (pinfunction "VBUS_B9") (pintype "unspecified"))
    )
    (net (code "82") (name "SET_EN") (class "Default")
      (node (ref "R73") (pin "1") (pinfunction "1_1") (pintype "input"))
      (node (ref "R75") (pin "2") (pinfunction "2_2") (pintype "input"))
      (node (ref "U21") (pin "6") (pinfunction "ENB_6") (pintype "unspecified"))
      (node (ref "U26") (pin "6") (pinfunction "ENB_6") (pintype "unspecified"))
      (node (ref "U27") (pin "6") (pinfunction "ENB_6") (pintype "unspecified"))
    )
    (net (code "83") (name "SGND") (class "Default")
      (node (ref "C1") (pin "1") (pinfunction "1_1") (pintype "input"))
      (node (ref "C18") (pin "2") (pinfunction "2_2") (pintype "unspecified"))
      (node (ref "C2") (pin "1") (pinfunction "1_1") (pintype "input"))
      (node (ref "C4") (pin "2") (pinfunction "2_2") (pintype "unspecified"))
      (node (ref "C7") (pin "1") (pinfunction "1_1") (pintype "input"))
      (node (ref "C8") (pin "1") (pinfunction "1_1") (pintype "input"))
      (node (ref "L4") (pin "2") (pinfunction "2_2") (pintype "unspecified"))
      (node (ref "L5") (pin "3") (pinfunction "3_3") (pintype "unspecified"))
      (node (ref "U11") (pin "6") (pinfunction "6_6") (pintype "unspecified"))
      (node (ref "U11") (pin "7") (pinfunction "7_7") (pintype "unspecified"))
      (node (ref "U14") (pin "1") (pinfunction "1_1") (pintype "unspecified"))
    )
    (net (code "84") (name "SIGNAL_A") (class "Default")
      (node (ref "C33") (pin "2") (pinfunction "2_2") (pintype "unspecified"))
      (node (ref "R41") (pin "1") (pinfunction "1_1") (pintype "input"))
      (node (ref "U15") (pin "4") (pinfunction "4_4") (pintype "unspecified"))
      (node (ref "U21") (pin "4") (pinfunction "B_4") (pintype "unspecified"))
    )
    (net (code "85") (name "SIGNAL_B") (class "Default")
      (node (ref "C34") (pin "2") (pinfunction "2_2") (pintype "unspecified"))
      (node (ref "C70") (pin "2") (pinfunction "2_2") (pintype "unspecified"))
      (node (ref "R50") (pin "1") (pinfunction "1_1") (pintype "unspecified"))
      (node (ref "R57") (pin "3") (pinfunction "3_3") (pintype "input"))
      (node (ref "U21") (pin "3") (pinfunction "A2_3") (pintype "unspecified"))
    )
    (net (code "86") (name "SIGNAL_C") (class "Default")
      (node (ref "C34") (pin "1") (pinfunction "1_1") (pintype "unspecified"))
      (node (ref "C70") (pin "1") (pinfunction "1_1") (pintype "unspecified"))
      (node (ref "R50") (pin "2") (pinfunction "2_2") (pintype "unspecified"))
      (node (ref "R57") (pin "1") (pinfunction "1_1") (pintype "input"))
      (node (ref "R57") (pin "2") (pinfunction "2_2") (pintype "input"))
      (node (ref "U26") (pin "4") (pinfunction "B_4") (pintype "unspecified"))
    )
    (net (code "87") (name "SIGNAL_D") (class "Default")
      (node (ref "C36") (pin "2") (pinfunction "2_2") (pintype "unspecified"))
      (node (ref "R56") (pin "1") (pinfunction "1_1") (pintype "input"))
      (node (ref "U17") (pin "4") (pinfunction "4_4") (pintype "unspecified"))
      (node (ref "U26") (pin "3") (pinfunction "A2_3") (pintype "unspecified"))
    )
    (net (code "88") (name "SIGNAL_OUT") (class "Default")
      (node (ref "C44") (pin "1") (pinfunction "1_1") (pintype "unspecified"))
      (node (ref "R47") (pin "2") (pinfunction "2_2") (pintype "unspecified"))
      (node (ref "R74") (pin "1") (pinfunction "1_1") (pintype "input"))
      (node (ref "RF1") (pin "5") (pinfunction "5_5") (pintype "unspecified"))
    )
    (net (code "89") (name "VBUS") (class "Default")
      (node (ref "C28") (pin "2") (pinfunction "2_2") (pintype "input"))
      (node (ref "D2") (pin "2") (pinfunction "A_2") (pintype "unspecified"))
      (node (ref "D5") (pin "1") (pinfunction "A_1") (pintype "unspecified"))
      (node (ref "L3") (pin "1") (pinfunction "1_1") (pintype "unspecified"))
    )
    (net (code "90") (name "VCC_BIAS") (class "Default")
      (node (ref "C23") (pin "1") (pinfunction "1_1") (pintype "unspecified"))
      (node (ref "R31") (pin "3") (pinfunction "3_3") (pintype "input"))
      (node (ref "R78") (pin "3") (pinfunction "3_3") (pintype "input"))
      (node (ref "R80") (pin "2") (pinfunction "2_2") (pintype "input"))
    )
    (net (code "91") (name "VSS_BIAS") (class "Default")
      (node (ref "C22") (pin "1") (pinfunction "1_1") (pintype "unspecified"))
      (node (ref "R31") (pin "1") (pinfunction "1_1") (pintype "input"))
      (node (ref "R78") (pin "1") (pinfunction "1_1") (pintype "input"))
      (node (ref "R81") (pin "2") (pinfunction "2_2") (pintype "input"))
    )
    (net (code "92") (name "unconnected-(SW1-Pad1)") (class "Default")
      (node (ref "SW1") (pin "1") (pinfunction "1_1") (pintype "unspecified+no_connect"))
    )
    (net (code "93") (name "unconnected-(U21-A1-Pad1)") (class "Default")
      (node (ref "U21") (pin "1") (pinfunction "A1_1") (pintype "unspecified+no_connect"))
    )
    (net (code "94") (name "unconnected-(U23-NC-Pad3)") (class "Default")
      (node (ref "U23") (pin "3") (pinfunction "NC_3") (pintype "unspecified+no_connect"))
    )
    (net (code "95") (name "unconnected-(U26-A1-Pad1)") (class "Default")
      (node (ref "U26") (pin "1") (pinfunction "A1_1") (pintype "unspecified+no_connect"))
    )
  )
)
